# SOM_EVAL_BOARD_V1_1.net
KiCad netlist of a schematic drawn in EAGLE
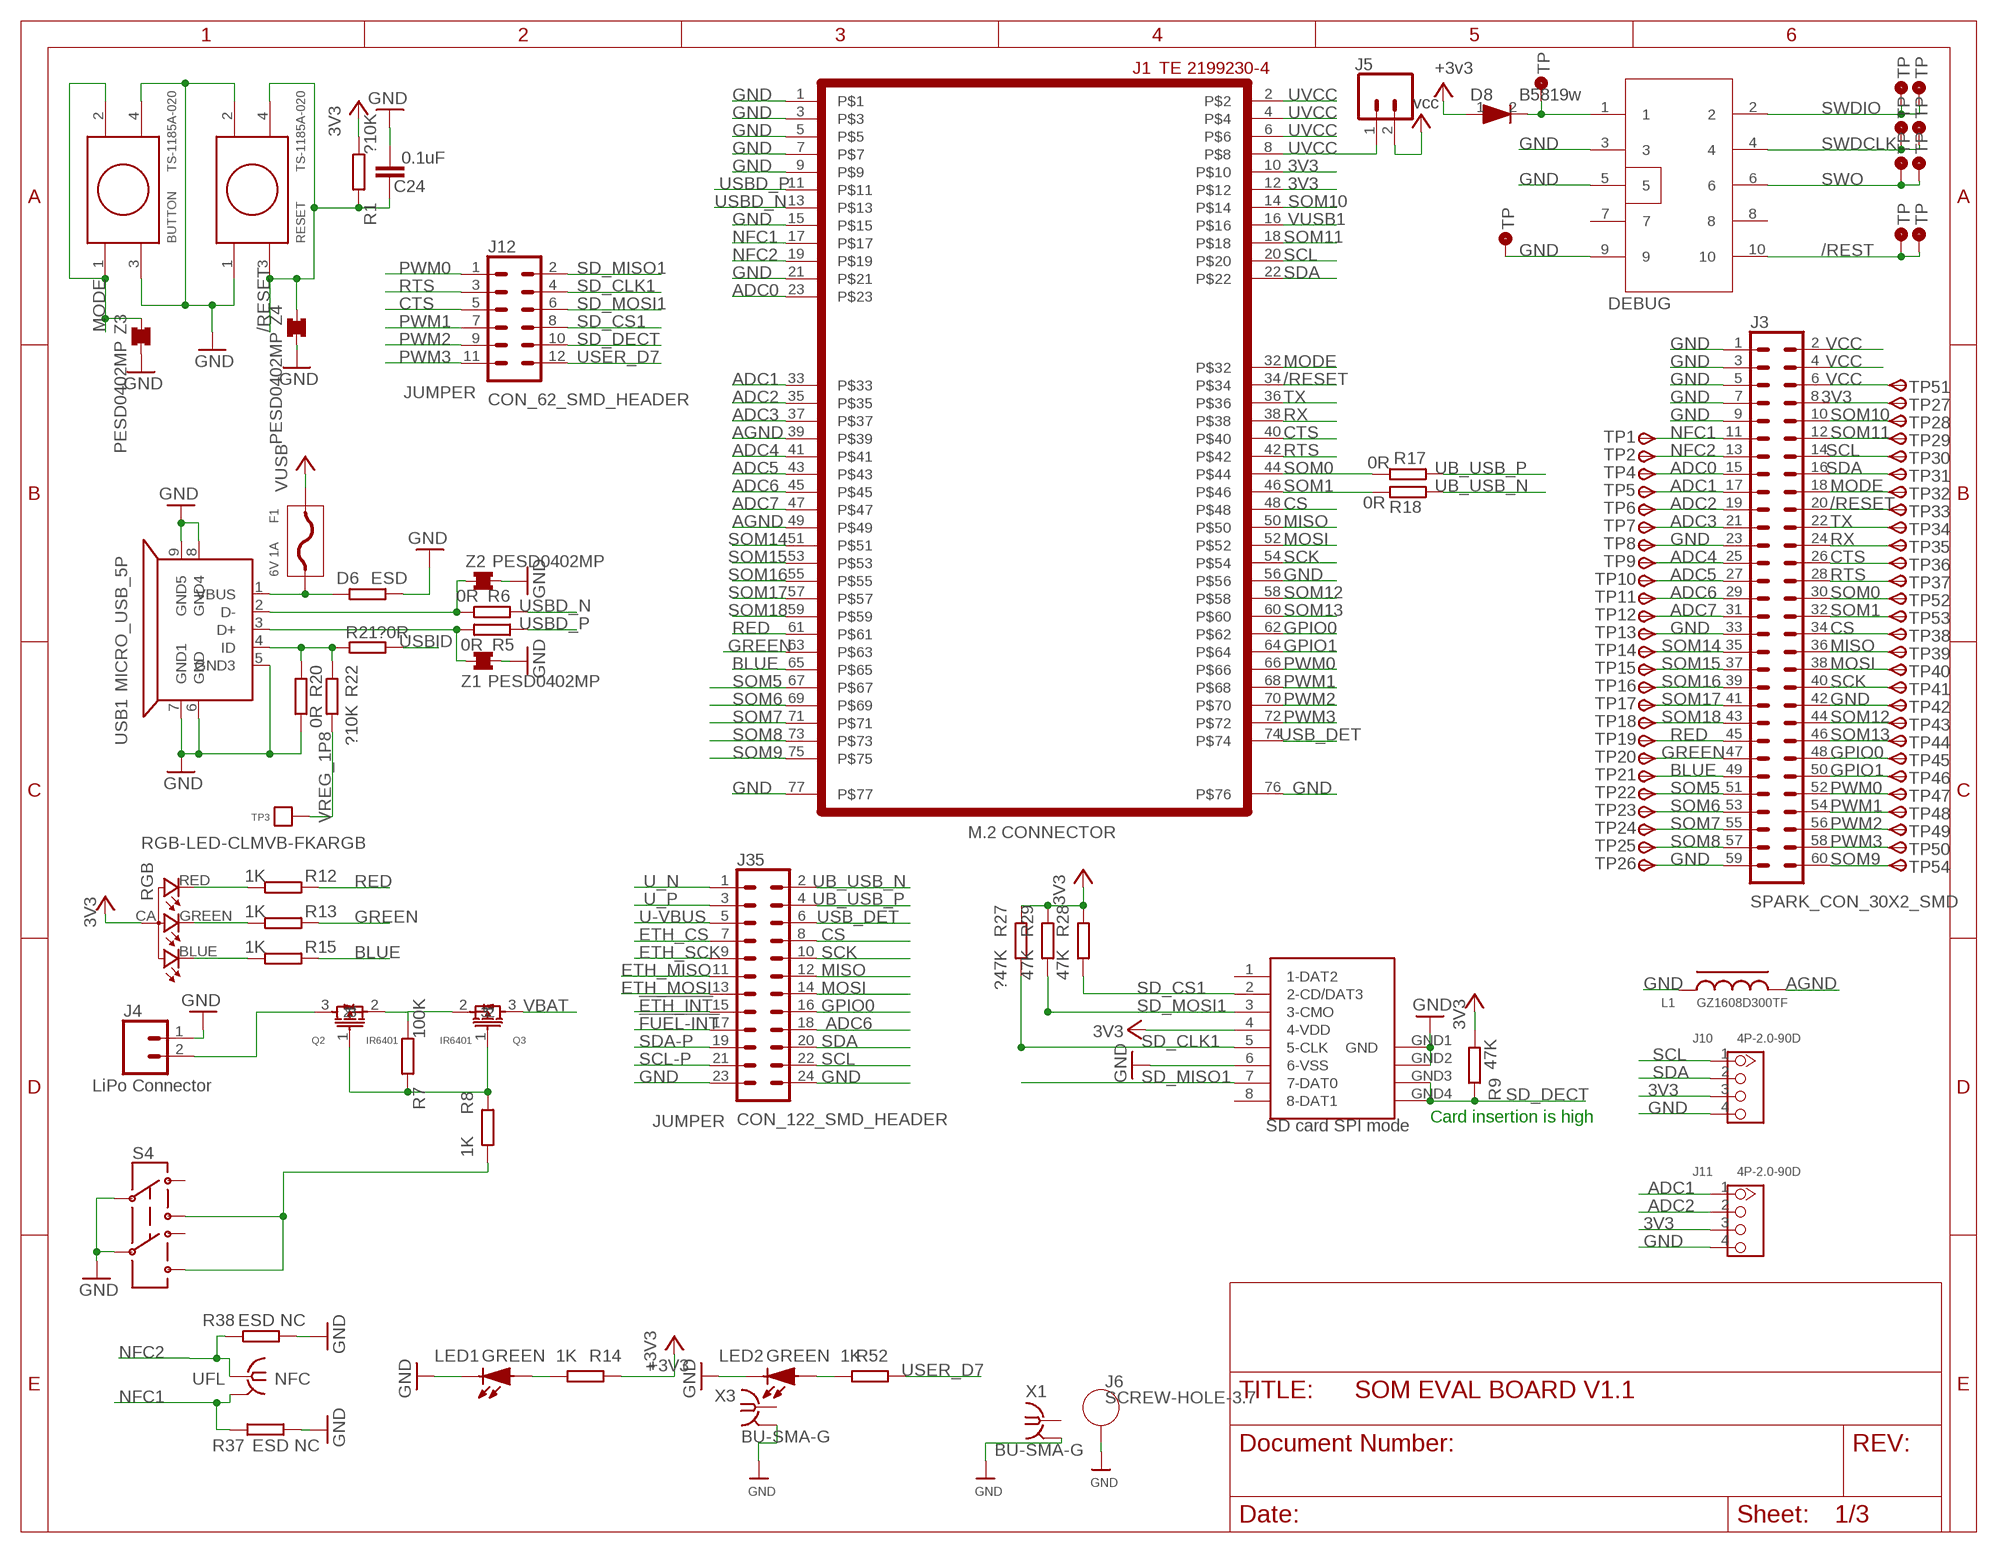
[diagram p0: schematic, sheet 1]
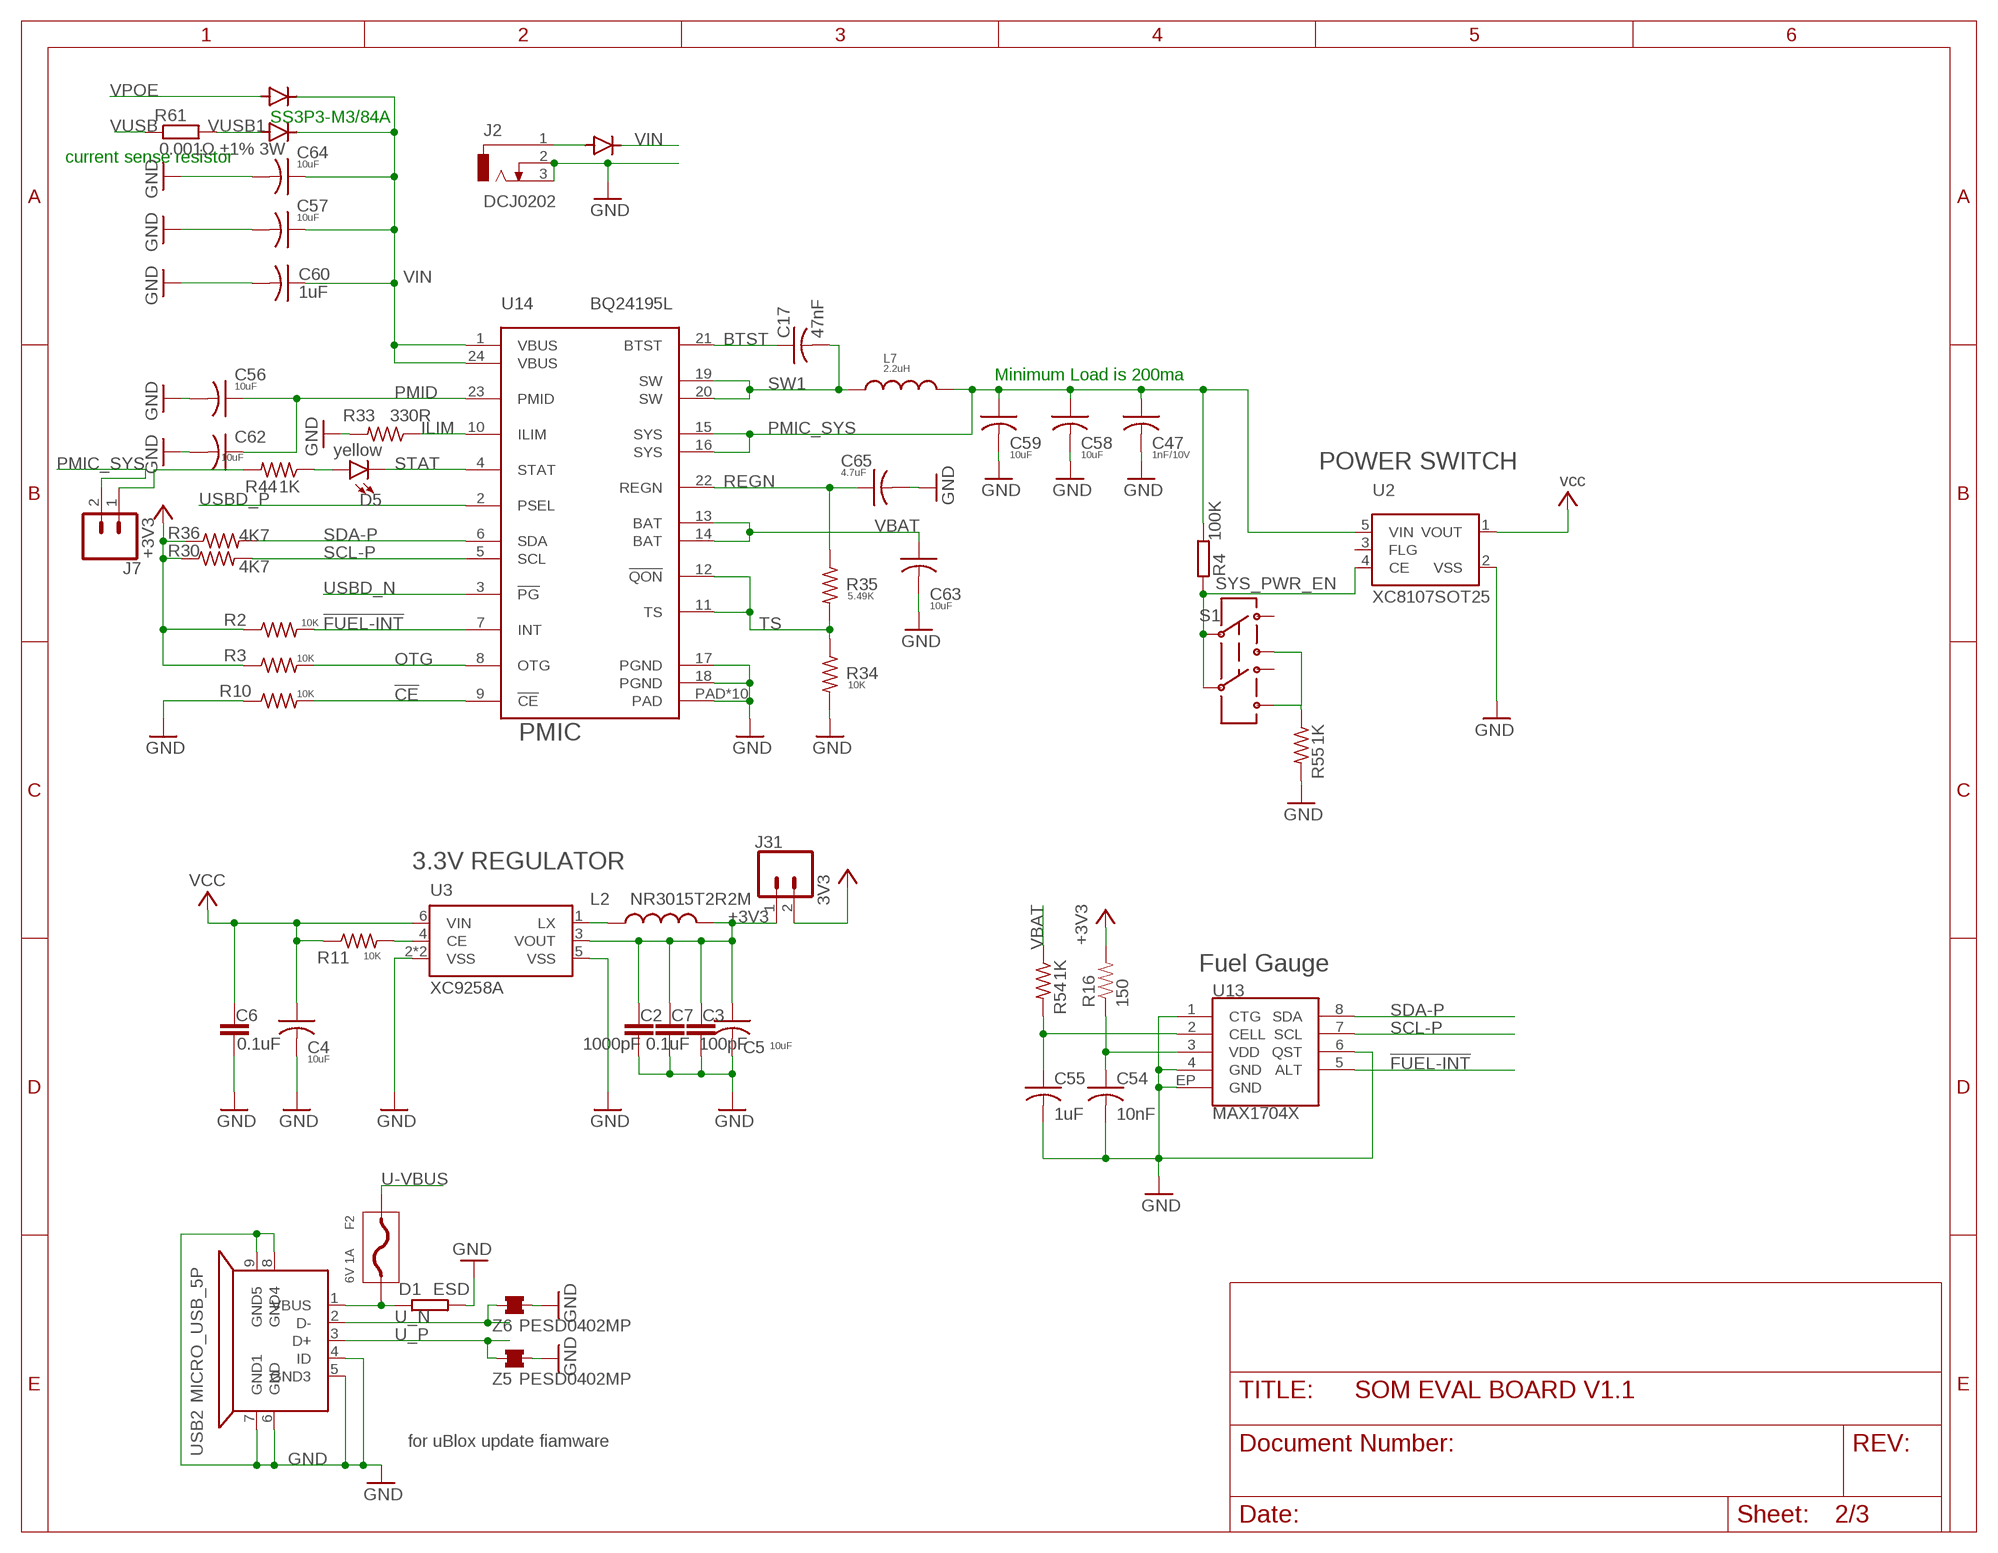
[diagram p1: schematic, sheet 2]
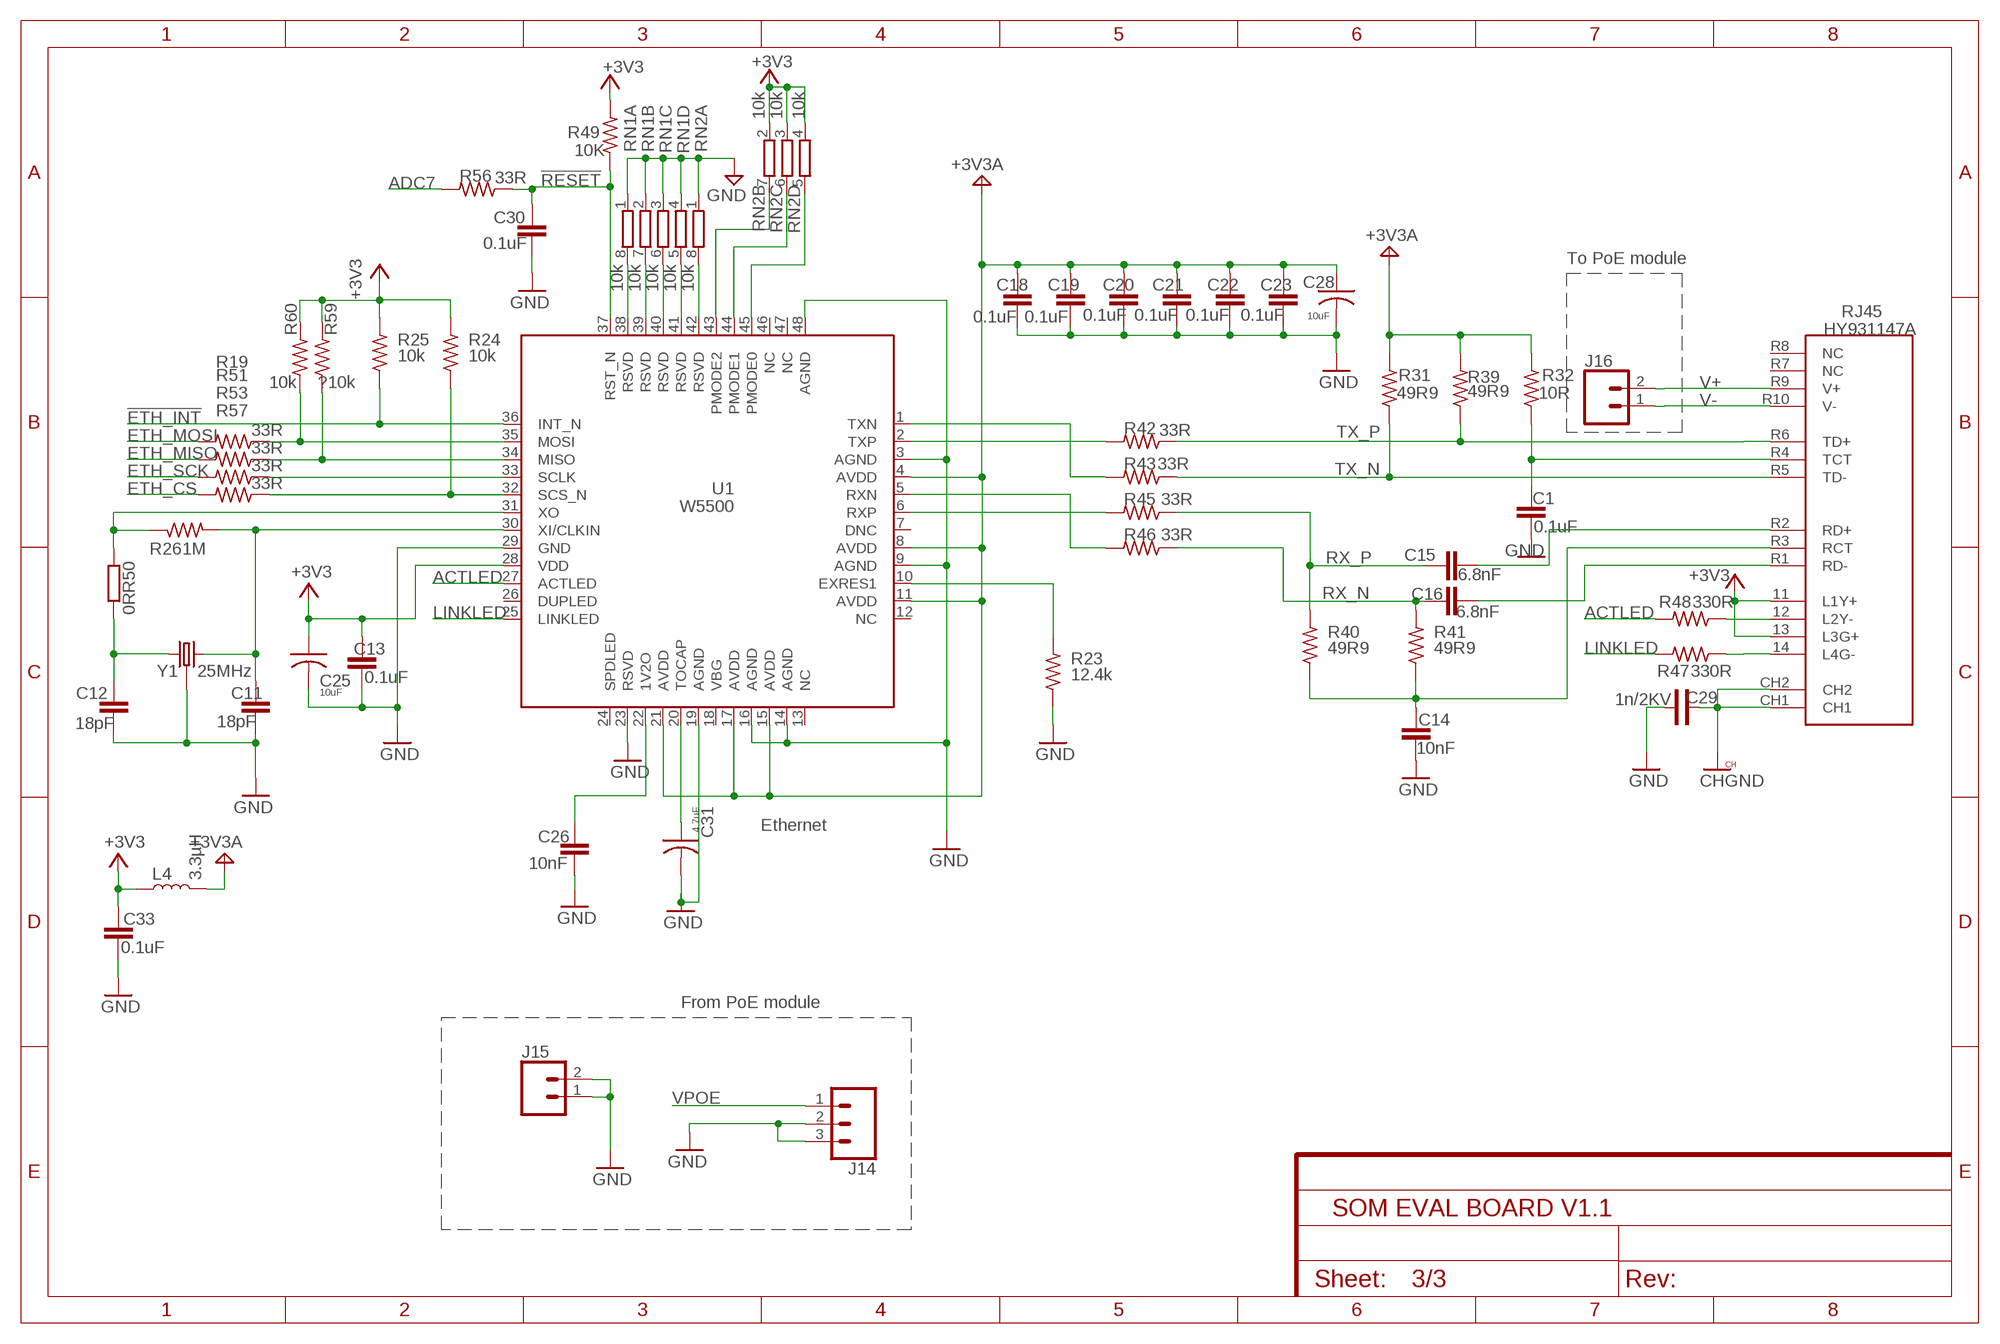
[diagram p2: schematic, sheet 3]

(export (version "E")
  (design (tool "Eeschema 10.0.6"))
  (components
    (comp (ref "C2")
      (value "1000pF")
      (footprint "eagle-import:C0402_B")
      (libsource (lib "eagle-import") (part "CAP_1"))
    )
    (comp (ref "C3")
      (value "100pF")
      (footprint "eagle-import:C0402_B")
      (libsource (lib "eagle-import") (part "CAP_1"))
    )
    (comp (ref "C4")
      (value "10uF")
      (footprint "eagle-import:C0603_B")
      (libsource (lib "eagle-import") (part "C-US0603"))
    )
    (comp (ref "C5")
      (value "10uF")
      (footprint "eagle-import:C0603_B")
      (libsource (lib "eagle-import") (part "C-US0603"))
    )
    (comp (ref "C6")
      (value "0.1uF")
      (footprint "eagle-import:C0402_B")
      (libsource (lib "eagle-import") (part "CAP_1"))
    )
    (comp (ref "C7")
      (value "0.1uF")
      (footprint "eagle-import:C0402_B")
      (libsource (lib "eagle-import") (part "CAP_1"))
    )
    (comp (ref "C17")
      (value "47nF")
      (footprint "eagle-import:C0201_B")
      (libsource (lib "eagle-import") (part "C-USC0201_B"))
    )
    (comp (ref "C47")
      (value "1nF/10V")
      (footprint "eagle-import:C0402_B")
      (libsource (lib "eagle-import") (part "C-US0402"))
    )
    (comp (ref "C54")
      (value "10nF")
      (footprint "eagle-import:C0402_B")
      (libsource (lib "eagle-import") (part "Spark_C-US"))
    )
    (comp (ref "C55")
      (value "1uF")
      (footprint "eagle-import:C0402_B")
      (libsource (lib "eagle-import") (part "Spark_C-US"))
    )
    (comp (ref "C56")
      (value "10uF")
      (footprint "eagle-import:C0603_B")
      (libsource (lib "eagle-import") (part "C-US0603"))
    )
    (comp (ref "C57")
      (value "10uF")
      (footprint "eagle-import:C0603_B")
      (libsource (lib "eagle-import") (part "C-US0603"))
    )
    (comp (ref "C58")
      (value "10uF")
      (footprint "eagle-import:C0603_B")
      (libsource (lib "eagle-import") (part "C-US0603"))
    )
    (comp (ref "C59")
      (value "10uF")
      (footprint "eagle-import:C0603_B")
      (libsource (lib "eagle-import") (part "C-US0603"))
    )
    (comp (ref "C60")
      (value "1uF")
      (footprint "eagle-import:C0402_B")
      (libsource (lib "eagle-import") (part "Spark_C-US"))
    )
    (comp (ref "C62")
      (value "10uF")
      (footprint "eagle-import:C0603_B")
      (libsource (lib "eagle-import") (part "C-US0603"))
    )
    (comp (ref "C63")
      (value "10uF")
      (footprint "eagle-import:C0603_B")
      (libsource (lib "eagle-import") (part "C-US0603"))
    )
    (comp (ref "C64")
      (value "10uF")
      (footprint "eagle-import:C0603_B")
      (libsource (lib "eagle-import") (part "C-US0603"))
    )
    (comp (ref "C65")
      (value "4.7uF")
      (footprint "eagle-import:C0603_B")
      (libsource (lib "eagle-import") (part "C-US0603"))
    )
    (comp (ref "D1")
      (value "ESD")
      (footprint "eagle-import:R-0402S")
      (libsource (lib "eagle-import") (part "RES0402S"))
    )
    (comp (ref "D3")
      (value "SS3P3-M3/84A")
      (footprint "eagle-import:DIODE-DO-220AA_NT(SMP)")
      (libsource (lib "eagle-import") (part "DIODE_NT"))
    )
    (comp (ref "D4")
      (value "SS3P3-M3/84A")
      (footprint "eagle-import:DIODE-DO-220AA_NT(SMP)")
      (libsource (lib "eagle-import") (part "DIODE_NT"))
    )
    (comp (ref "D5")
      (value "yellow")
      (footprint "eagle-import:LED-0603")
      (libsource (lib "eagle-import") (part "LED-RED0603"))
    )
    (comp (ref "D7")
      (value "SS3P3-M3/84A")
      (footprint "eagle-import:DIODE-DO-220AA_NT(SMP)")
      (libsource (lib "eagle-import") (part "DIODE_NT"))
    )
    (comp (ref "F2")
      (value "6V 1A")
      (footprint "eagle-import:F0805")
      (libsource (lib "eagle-import") (part "FUSE"))
    )
    (comp (ref "J2")
      (value "DCJ0202")
      (footprint "eagle-import:DCJ0202")
      (libsource (lib "eagle-import") (part "DCJ0202"))
    )
    (comp (ref "J7")
      (value "CONN_02")
      (footprint "eagle-import:1X02")
      (libsource (lib "eagle-import") (part "SparkFun-Connectors_513_CONN_02"))
    )
    (comp (ref "J31")
      (value "CONN_02")
      (footprint "eagle-import:1X02")
      (libsource (lib "eagle-import") (part "SparkFun-Connectors_513_CONN_02"))
    )
    (comp (ref "L2")
      (value "NR3015T2R2M")
      (footprint "eagle-import:INDUCTOR-VLS-E")
      (libsource (lib "eagle-import") (part "INDUCTOR-SPARKFUNVLS3012ET-4R7M"))
    )
    (comp (ref "L7")
      (value "2.2uH")
      (footprint "eagle-import:INDUCTOR-4040")
      (libsource (lib "eagle-import") (part "INDUCTORI"))
    )
    (comp (ref "R2")
      (value "10K")
      (footprint "eagle-import:R0402_B")
      (libsource (lib "eagle-import") (part "Spark_R-US_"))
    )
    (comp (ref "R3")
      (value "10K")
      (footprint "eagle-import:R0402_B")
      (libsource (lib "eagle-import") (part "Spark_R-US_"))
    )
    (comp (ref "R4")
      (value "100K")
      (footprint "eagle-import:R0603")
      (libsource (lib "eagle-import") (part "RESR0603"))
    )
    (comp (ref "R10")
      (value "10K")
      (footprint "eagle-import:R0402_B")
      (libsource (lib "eagle-import") (part "Spark_R-US_"))
    )
    (comp (ref "R11")
      (value "10K")
      (footprint "eagle-import:R0402_B")
      (libsource (lib "eagle-import") (part "Spark_R-US_"))
    )
    (comp (ref "R16")
      (value "150")
      (footprint "eagle-import:0402-RES")
      (libsource (lib "eagle-import") (part "RESISTOR0402-RES"))
    )
    (comp (ref "R30")
      (value "4K7")
      (footprint "eagle-import:C0201_B")
      (libsource (lib "eagle-import") (part "R-US_R0201_B"))
    )
    (comp (ref "R33")
      (value "330R")
      (footprint "eagle-import:R0402_B")
      (libsource (lib "eagle-import") (part "R-US_"))
    )
    (comp (ref "R34")
      (value "10K")
      (footprint "eagle-import:R0402_B")
      (libsource (lib "eagle-import") (part "Spark_R-US_"))
    )
    (comp (ref "R35")
      (value "5.49K")
      (footprint "eagle-import:R0402_B")
      (libsource (lib "eagle-import") (part "Spark_R-US_"))
    )
    (comp (ref "R36")
      (value "4K7")
      (footprint "eagle-import:C0201_B")
      (libsource (lib "eagle-import") (part "R-US_R0201_B"))
    )
    (comp (ref "R44")
      (value "1K")
      (footprint "eagle-import:R0402_B")
      (libsource (lib "eagle-import") (part "R-US_"))
    )
    (comp (ref "R54")
      (value "1K")
      (footprint "eagle-import:R0402_B")
      (libsource (lib "eagle-import") (part "R-US_"))
    )
    (comp (ref "R55")
      (value "1K")
      (footprint "eagle-import:R0402_B")
      (libsource (lib "eagle-import") (part "R-US_"))
    )
    (comp (ref "R61")
      (value "0.001Ω ±1% 3W")
      (footprint "eagle-import:R2512")
      (libsource (lib "eagle-import") (part "R-EU_R2512"))
    )
    (comp (ref "S1")
      (value "SWITCH-DPDT")
      (footprint "eagle-import:SWITCH-2.5X3.2-6")
      (libsource (lib "eagle-import") (part "SWITCH-DPDT"))
    )
    (comp (ref "U2")
      (value "XC8107SOT25")
      (footprint "eagle-import:SOT25")
      (libsource (lib "eagle-import") (part "XC8107SOT25"))
    )
    (comp (ref "U3")
      (value "XC9258A")
      (footprint "eagle-import:USP-6C")
      (libsource (lib "eagle-import") (part "XC9258A33EER-G"))
    )
    (comp (ref "U13")
      (value "MAX1704X")
      (footprint "eagle-import:TDFN-8")
      (libsource (lib "eagle-import") (part "MAX1704X"))
    )
    (comp (ref "U14")
      (value "BQ24195L")
      (footprint "eagle-import:QFN24")
      (libsource (lib "eagle-import") (part "BQ24298RTWR"))
    )
    (comp (ref "USB2")
      (value "MICRO_USB_5P")
      (footprint "eagle-import:MICRO_USB")
      (libsource (lib "eagle-import") (part "MICRO_USBMICRO_USB"))
    )
    (comp (ref "Z5")
      (value "PESD0402MP")
      (footprint "eagle-import:SMD-0402MP")
      (libsource (lib "eagle-import") (part "PESD0402MP"))
    )
    (comp (ref "Z6")
      (value "PESD0402MP")
      (footprint "eagle-import:SMD-0402MP")
      (libsource (lib "eagle-import") (part "PESD0402MP"))
    )
    (comp (ref "BUTTON")
      (value "TS-1185A-020")
      (footprint "eagle-import:TS-1185A-020")
      (libsource (lib "eagle-import") (part "TS-1185A-020"))
    )
    (comp (ref "C24")
      (value "0.1uF")
      (footprint "eagle-import:C0402_B")
      (libsource (lib "eagle-import") (part "CAP_1"))
    )
    (comp (ref "D6")
      (value "ESD")
      (footprint "eagle-import:R-0402S")
      (libsource (lib "eagle-import") (part "RES0402S"))
    )
    (comp (ref "D8")
      (value "B5819w")
      (footprint "eagle-import:SOD-123")
      (libsource (lib "eagle-import") (part "DIODESOD123"))
    )
    (comp (ref "DEBUG")
      (value "CON5X2")
      (footprint "eagle-import:CON5X2_1.27")
      (libsource (lib "eagle-import") (part "CON5X2"))
    )
    (comp (ref "F1")
      (value "6V 1A")
      (footprint "eagle-import:F0805")
      (libsource (lib "eagle-import") (part "FUSE"))
    )
    (comp (ref "J1")
      (value "TE 2199230-4")
      (footprint "eagle-import:M.2EKEY")
      (libsource (lib "eagle-import") (part "M.2EKEY"))
    )
    (comp (ref "J3")
      (value "SPARK_CON_30X2_SMD")
      (footprint "eagle-import:SPARK_CON_30X2_SMD")
      (libsource (lib "eagle-import") (part "SPARK_CON_30X2_SMD"))
    )
    (comp (ref "J4")
      (value "CONN_02-JST-2MM-SMT")
      (footprint "eagle-import:JST-2-SMD")
      (libsource (lib "eagle-import") (part "CONN_02-JST-2MM-SMT"))
    )
    (comp (ref "J5")
      (value "CONN_02")
      (footprint "eagle-import:1X02")
      (libsource (lib "eagle-import") (part "SparkFun-Connectors_513_CONN_02"))
    )
    (comp (ref "J6")
      (value "SCREW-HOLE-3.7")
      (footprint "eagle-import:SCREW-HOLE-3.7")
      (libsource (lib "eagle-import") (part "SCREW-HOLE-3.7"))
    )
    (comp (ref "J10")
      (value "4P-2.0-90D")
      (footprint "eagle-import:HW4-2.0-90D")
      (libsource (lib "eagle-import") (part "GROVE-CONNECTOR-DIP-90D(4P-2.0)"))
    )
    (comp (ref "J11")
      (value "4P-2.0-90D")
      (footprint "eagle-import:HW4-2.0-90D")
      (libsource (lib "eagle-import") (part "GROVE-CONNECTOR-DIP-90D(4P-2.0)"))
    )
    (comp (ref "J12")
      (value "CON_62_SMD_HEADER")
      (footprint "eagle-import:CON_6_2_SMD_HEADER")
      (libsource (lib "eagle-import") (part "CON_62_SMD_HEADER"))
    )
    (comp (ref "J35")
      (value "CON_122_SMD_HEADER")
      (footprint "eagle-import:CON_12_2_SMD_HEADER")
      (libsource (lib "eagle-import") (part "CON_122_SMD_HEADER"))
    )
    (comp (ref "L1")
      (value "GZ1608D300TF")
      (footprint "eagle-import:R-0603A")
      (libsource (lib "eagle-import") (part "L"))
    )
    (comp (ref "LED1")
      (value "GREEN")
      (footprint "eagle-import:LED0603")
      (libsource (lib "eagle-import") (part "LED"))
    )
    (comp (ref "LED2")
      (value "GREEN")
      (footprint "eagle-import:LED0603")
      (libsource (lib "eagle-import") (part "LED"))
    )
    (comp (ref "NFC")
      (value "UFL")
      (footprint "eagle-import:IPEX-20279-001E")
      (libsource (lib "eagle-import") (part "IPEX-20279-001E"))
    )
    (comp (ref "P1")
      (value "SPARK_POGOPIN")
      (footprint "eagle-import:SPARK_POGO-2.0")
      (libsource (lib "eagle-import") (part "SPARK_POGOPIN"))
    )
    (comp (ref "P2")
      (value "SPARK_POGOPIN")
      (footprint "eagle-import:SPARK_POGO-2.0")
      (libsource (lib "eagle-import") (part "SPARK_POGOPIN"))
    )
    (comp (ref "P3")
      (value "SPARK_POGOPIN")
      (footprint "eagle-import:SPARK_POGO-2.0")
      (libsource (lib "eagle-import") (part "SPARK_POGOPIN"))
    )
    (comp (ref "P4")
      (value "SPARK_POGOPIN")
      (footprint "eagle-import:SPARK_POGO-2.0")
      (libsource (lib "eagle-import") (part "SPARK_POGOPIN"))
    )
    (comp (ref "Q2")
      (value "IR6401")
      (footprint "eagle-import:SOT-23")
      (libsource (lib "eagle-import") (part "PMOS"))
    )
    (comp (ref "Q3")
      (value "IR6401")
      (footprint "eagle-import:SOT-23")
      (libsource (lib "eagle-import") (part "PMOS"))
    )
    (comp (ref "R1")
      (value "?10K")
      (footprint "eagle-import:R-0402S")
      (libsource (lib "eagle-import") (part "RES0402S"))
    )
    (comp (ref "R5")
      (value "0R")
      (footprint "eagle-import:R-0402S")
      (libsource (lib "eagle-import") (part "RES0402S"))
    )
    (comp (ref "R6")
      (value "0R")
      (footprint "eagle-import:R-0402S")
      (libsource (lib "eagle-import") (part "RES0402S"))
    )
    (comp (ref "R7")
      (value "100K")
      (footprint "eagle-import:R0603")
      (libsource (lib "eagle-import") (part "RESR0603"))
    )
    (comp (ref "R8")
      (value "1K")
      (footprint "eagle-import:R-0402S")
      (libsource (lib "eagle-import") (part "RES0402S"))
    )
    (comp (ref "R9")
      (value "47K")
      (footprint "eagle-import:R-0402S")
      (libsource (lib "eagle-import") (part "RES0402S"))
    )
    (comp (ref "R12")
      (value "1K")
      (footprint "eagle-import:R-0402S")
      (libsource (lib "eagle-import") (part "RES0402S"))
    )
    (comp (ref "R13")
      (value "1K")
      (footprint "eagle-import:R-0402S")
      (libsource (lib "eagle-import") (part "RES0402S"))
    )
    (comp (ref "R14")
      (value "1K")
      (footprint "eagle-import:R-0402S")
      (libsource (lib "eagle-import") (part "RES0402S"))
    )
    (comp (ref "R15")
      (value "1K")
      (footprint "eagle-import:R-0402S")
      (libsource (lib "eagle-import") (part "RES0402S"))
    )
    (comp (ref "R17")
      (value "0R")
      (footprint "eagle-import:R-0402S")
      (libsource (lib "eagle-import") (part "RES0402S"))
    )
    (comp (ref "R18")
      (value "0R")
      (footprint "eagle-import:R-0402S")
      (libsource (lib "eagle-import") (part "RES0402S"))
    )
    (comp (ref "R20")
      (value "0R")
      (footprint "eagle-import:R-0402S")
      (libsource (lib "eagle-import") (part "RES0402S"))
    )
    (comp (ref "R21")
      (value "?0R")
      (footprint "eagle-import:R-0402S")
      (libsource (lib "eagle-import") (part "RES0402S"))
    )
    (comp (ref "R22")
      (value "?10K")
      (footprint "eagle-import:R-0402S")
      (libsource (lib "eagle-import") (part "RES0402S"))
    )
    (comp (ref "R27")
      (value "?47K")
      (footprint "eagle-import:R-0402S")
      (libsource (lib "eagle-import") (part "RES0402S"))
    )
    (comp (ref "R28")
      (value "47K")
      (footprint "eagle-import:R-0402S")
      (libsource (lib "eagle-import") (part "RES0402S"))
    )
    (comp (ref "R29")
      (value "47K")
      (footprint "eagle-import:R-0402S")
      (libsource (lib "eagle-import") (part "RES0402S"))
    )
    (comp (ref "R37")
      (value "ESD NC")
      (footprint "eagle-import:R-0402S")
      (libsource (lib "eagle-import") (part "RES0402S"))
    )
    (comp (ref "R38")
      (value "ESD NC")
      (footprint "eagle-import:R-0402S")
      (libsource (lib "eagle-import") (part "RES0402S"))
    )
    (comp (ref "R52")
      (value "1K")
      (footprint "eagle-import:R-0402S")
      (libsource (lib "eagle-import") (part "RES0402S"))
    )
    (comp (ref "RESET")
      (value "TS-1185A-020")
      (footprint "eagle-import:TS-1185A-020")
      (libsource (lib "eagle-import") (part "TS-1185A-020"))
    )
    (comp (ref "RGB")
      (value "RGB-LED-CLMVB-FKARGB")
      (footprint "eagle-import:PLCC4-2MM-RGB")
      (libsource (lib "eagle-import") (part "RGB-LED-CLMVB-FKARGB"))
    )
    (comp (ref "S4")
      (value "SWITCH-DPDT")
      (footprint "eagle-import:SWITCH-2.5X3.2-6")
      (libsource (lib "eagle-import") (part "SWITCH-DPDT"))
    )
    (comp (ref "TP1")
      (value "TPSB1,27")
      (footprint "eagle-import:B1,27")
      (libsource (lib "eagle-import") (part "TPSB1,27"))
    )
    (comp (ref "TP2")
      (value "TPSB1,27")
      (footprint "eagle-import:B1,27")
      (libsource (lib "eagle-import") (part "TPSB1,27"))
    )
    (comp (ref "TP3")
      (value "TPTP")
      (footprint "eagle-import:TP")
      (libsource (lib "eagle-import") (part "TPTP"))
    )
    (comp (ref "TP4")
      (value "TPSB1,27")
      (footprint "eagle-import:B1,27")
      (libsource (lib "eagle-import") (part "TPSB1,27"))
    )
    (comp (ref "TP5")
      (value "TPSB1,27")
      (footprint "eagle-import:B1,27")
      (libsource (lib "eagle-import") (part "TPSB1,27"))
    )
    (comp (ref "TP6")
      (value "TPSB1,27")
      (footprint "eagle-import:B1,27")
      (libsource (lib "eagle-import") (part "TPSB1,27"))
    )
    (comp (ref "TP7")
      (value "TPSB1,27")
      (footprint "eagle-import:B1,27")
      (libsource (lib "eagle-import") (part "TPSB1,27"))
    )
    (comp (ref "TP8")
      (value "TPSB1,27")
      (footprint "eagle-import:B1,27")
      (libsource (lib "eagle-import") (part "TPSB1,27"))
    )
    (comp (ref "TP9")
      (value "TPSB1,27")
      (footprint "eagle-import:B1,27")
      (libsource (lib "eagle-import") (part "TPSB1,27"))
    )
    (comp (ref "TP10")
      (value "TPSB1,27")
      (footprint "eagle-import:B1,27")
      (libsource (lib "eagle-import") (part "TPSB1,27"))
    )
    (comp (ref "TP11")
      (value "TPSB1,27")
      (footprint "eagle-import:B1,27")
      (libsource (lib "eagle-import") (part "TPSB1,27"))
    )
    (comp (ref "TP12")
      (value "TPSB1,27")
      (footprint "eagle-import:B1,27")
      (libsource (lib "eagle-import") (part "TPSB1,27"))
    )
    (comp (ref "TP13")
      (value "TPSB1,27")
      (footprint "eagle-import:B1,27")
      (libsource (lib "eagle-import") (part "TPSB1,27"))
    )
    (comp (ref "TP14")
      (value "TPSB1,27")
      (footprint "eagle-import:B1,27")
      (libsource (lib "eagle-import") (part "TPSB1,27"))
    )
    (comp (ref "TP15")
      (value "TPSB1,27")
      (footprint "eagle-import:B1,27")
      (libsource (lib "eagle-import") (part "TPSB1,27"))
    )
    (comp (ref "TP16")
      (value "TPSB1,27")
      (footprint "eagle-import:B1,27")
      (libsource (lib "eagle-import") (part "TPSB1,27"))
    )
    (comp (ref "TP17")
      (value "TPSB1,27")
      (footprint "eagle-import:B1,27")
      (libsource (lib "eagle-import") (part "TPSB1,27"))
    )
    (comp (ref "TP18")
      (value "TPSB1,27")
      (footprint "eagle-import:B1,27")
      (libsource (lib "eagle-import") (part "TPSB1,27"))
    )
    (comp (ref "TP19")
      (value "TPSB1,27")
      (footprint "eagle-import:B1,27")
      (libsource (lib "eagle-import") (part "TPSB1,27"))
    )
    (comp (ref "TP20")
      (value "TPSB1,27")
      (footprint "eagle-import:B1,27")
      (libsource (lib "eagle-import") (part "TPSB1,27"))
    )
    (comp (ref "TP21")
      (value "TPSB1,27")
      (footprint "eagle-import:B1,27")
      (libsource (lib "eagle-import") (part "TPSB1,27"))
    )
    (comp (ref "TP22")
      (value "TPSB1,27")
      (footprint "eagle-import:B1,27")
      (libsource (lib "eagle-import") (part "TPSB1,27"))
    )
    (comp (ref "TP23")
      (value "TPSB1,27")
      (footprint "eagle-import:B1,27")
      (libsource (lib "eagle-import") (part "TPSB1,27"))
    )
    (comp (ref "TP24")
      (value "TPSB1,27")
      (footprint "eagle-import:B1,27")
      (libsource (lib "eagle-import") (part "TPSB1,27"))
    )
    (comp (ref "TP25")
      (value "TPSB1,27")
      (footprint "eagle-import:B1,27")
      (libsource (lib "eagle-import") (part "TPSB1,27"))
    )
    (comp (ref "TP26")
      (value "TPSB1,27")
      (footprint "eagle-import:B1,27")
      (libsource (lib "eagle-import") (part "TPSB1,27"))
    )
    (comp (ref "TP27")
      (value "TPSB1,27")
      (footprint "eagle-import:B1,27")
      (libsource (lib "eagle-import") (part "TPSB1,27"))
    )
    (comp (ref "TP28")
      (value "TPSB1,27")
      (footprint "eagle-import:B1,27")
      (libsource (lib "eagle-import") (part "TPSB1,27"))
    )
    (comp (ref "TP29")
      (value "TPSB1,27")
      (footprint "eagle-import:B1,27")
      (libsource (lib "eagle-import") (part "TPSB1,27"))
    )
    (comp (ref "TP30")
      (value "TPSB1,27")
      (footprint "eagle-import:B1,27")
      (libsource (lib "eagle-import") (part "TPSB1,27"))
    )
    (comp (ref "TP31")
      (value "TPSB1,27")
      (footprint "eagle-import:B1,27")
      (libsource (lib "eagle-import") (part "TPSB1,27"))
    )
    (comp (ref "TP32")
      (value "TPSB1,27")
      (footprint "eagle-import:B1,27")
      (libsource (lib "eagle-import") (part "TPSB1,27"))
    )
    (comp (ref "TP33")
      (value "TPSB1,27")
      (footprint "eagle-import:B1,27")
      (libsource (lib "eagle-import") (part "TPSB1,27"))
    )
    (comp (ref "TP34")
      (value "TPSB1,27")
      (footprint "eagle-import:B1,27")
      (libsource (lib "eagle-import") (part "TPSB1,27"))
    )
    (comp (ref "TP35")
      (value "TPSB1,27")
      (footprint "eagle-import:B1,27")
      (libsource (lib "eagle-import") (part "TPSB1,27"))
    )
    (comp (ref "TP36")
      (value "TPSB1,27")
      (footprint "eagle-import:B1,27")
      (libsource (lib "eagle-import") (part "TPSB1,27"))
    )
    (comp (ref "TP37")
      (value "TPSB1,27")
      (footprint "eagle-import:B1,27")
      (libsource (lib "eagle-import") (part "TPSB1,27"))
    )
    (comp (ref "TP38")
      (value "TPSB1,27")
      (footprint "eagle-import:B1,27")
      (libsource (lib "eagle-import") (part "TPSB1,27"))
    )
    (comp (ref "TP39")
      (value "TPSB1,27")
      (footprint "eagle-import:B1,27")
      (libsource (lib "eagle-import") (part "TPSB1,27"))
    )
    (comp (ref "TP40")
      (value "TPSB1,27")
      (footprint "eagle-import:B1,27")
      (libsource (lib "eagle-import") (part "TPSB1,27"))
    )
    (comp (ref "TP41")
      (value "TPSB1,27")
      (footprint "eagle-import:B1,27")
      (libsource (lib "eagle-import") (part "TPSB1,27"))
    )
    (comp (ref "TP42")
      (value "TPSB1,27")
      (footprint "eagle-import:B1,27")
      (libsource (lib "eagle-import") (part "TPSB1,27"))
    )
    (comp (ref "TP43")
      (value "TPSB1,27")
      (footprint "eagle-import:B1,27")
      (libsource (lib "eagle-import") (part "TPSB1,27"))
    )
    (comp (ref "TP44")
      (value "TPSB1,27")
      (footprint "eagle-import:B1,27")
      (libsource (lib "eagle-import") (part "TPSB1,27"))
    )
    (comp (ref "TP45")
      (value "TPSB1,27")
      (footprint "eagle-import:B1,27")
      (libsource (lib "eagle-import") (part "TPSB1,27"))
    )
    (comp (ref "TP46")
      (value "TPSB1,27")
      (footprint "eagle-import:B1,27")
      (libsource (lib "eagle-import") (part "TPSB1,27"))
    )
    (comp (ref "TP47")
      (value "TPSB1,27")
      (footprint "eagle-import:B1,27")
      (libsource (lib "eagle-import") (part "TPSB1,27"))
    )
    (comp (ref "TP48")
      (value "TPSB1,27")
      (footprint "eagle-import:B1,27")
      (libsource (lib "eagle-import") (part "TPSB1,27"))
    )
    (comp (ref "TP49")
      (value "TPSB1,27")
      (footprint "eagle-import:B1,27")
      (libsource (lib "eagle-import") (part "TPSB1,27"))
    )
    (comp (ref "TP50")
      (value "TPSB1,27")
      (footprint "eagle-import:B1,27")
      (libsource (lib "eagle-import") (part "TPSB1,27"))
    )
    (comp (ref "TP51")
      (value "TPSB1,27")
      (footprint "eagle-import:B1,27")
      (libsource (lib "eagle-import") (part "TPSB1,27"))
    )
    (comp (ref "TP52")
      (value "TPSB1,27")
      (footprint "eagle-import:B1,27")
      (libsource (lib "eagle-import") (part "TPSB1,27"))
    )
    (comp (ref "TP53")
      (value "TPSB1,27")
      (footprint "eagle-import:B1,27")
      (libsource (lib "eagle-import") (part "TPSB1,27"))
    )
    (comp (ref "TP54")
      (value "TPSB1,27")
      (footprint "eagle-import:B1,27")
      (libsource (lib "eagle-import") (part "TPSB1,27"))
    )
    (comp (ref "U$1")
      (value "TP2")
      (footprint "eagle-import:TP70_BOT")
      (libsource (lib "eagle-import") (part "TP2"))
    )
    (comp (ref "U$2")
      (value "TP2")
      (footprint "eagle-import:TP70_BOT")
      (libsource (lib "eagle-import") (part "TP2"))
    )
    (comp (ref "U$9")
      (value "TP2")
      (footprint "eagle-import:TP70_BOT")
      (libsource (lib "eagle-import") (part "TP2"))
    )
    (comp (ref "U$10")
      (value "TP2")
      (footprint "eagle-import:TP70_BOT")
      (libsource (lib "eagle-import") (part "TP2"))
    )
    (comp (ref "U$11")
      (value "TP2")
      (footprint "eagle-import:TP70_BOT")
      (libsource (lib "eagle-import") (part "TP2"))
    )
    (comp (ref "U$12")
      (value "TP2")
      (footprint "eagle-import:TP70_BOT")
      (libsource (lib "eagle-import") (part "TP2"))
    )
    (comp (ref "USB1")
      (value "MICRO_USB_5P")
      (footprint "eagle-import:MICRO_USB")
      (libsource (lib "eagle-import") (part "MICRO_USBMICRO_USB"))
    )
    (comp (ref "X1")
      (value "BU-SMA-G")
      (footprint "eagle-import:BU-SMA-G")
      (libsource (lib "eagle-import") (part "BU-SMA-G"))
    )
    (comp (ref "X3")
      (value "BU-SMA-G")
      (footprint "eagle-import:BU-SMA-G")
      (libsource (lib "eagle-import") (part "BU-SMA-G"))
    )
    (comp (ref "X4")
      (value "0046_15TW-882")
      (footprint "eagle-import:SDCARD-15TW-8821")
      (fields (field (name "PART_NUMBER") "15TW-882 REEL"))
      (libsource (lib "eagle-import") (part "0046_15TW-882"))
    )
    (comp (ref "Z1")
      (value "PESD0402MP")
      (footprint "eagle-import:SMD-0402MP")
      (libsource (lib "eagle-import") (part "PESD0402MP"))
    )
    (comp (ref "Z2")
      (value "PESD0402MP")
      (footprint "eagle-import:SMD-0402MP")
      (libsource (lib "eagle-import") (part "PESD0402MP"))
    )
    (comp (ref "Z3")
      (value "PESD0402MP")
      (footprint "eagle-import:SMD-0402MP")
      (libsource (lib "eagle-import") (part "PESD0402MP"))
    )
    (comp (ref "Z4")
      (value "PESD0402MP")
      (footprint "eagle-import:SMD-0402MP")
      (libsource (lib "eagle-import") (part "PESD0402MP"))
    )
    (comp (ref "C1")
      (value "0.1uF")
      (footprint "eagle-import:C0402_B")
      (libsource (lib "eagle-import") (part "CAP_1"))
    )
    (comp (ref "C11")
      (value "18pF")
      (footprint "eagle-import:C0402_B")
      (libsource (lib "eagle-import") (part "CAP_1"))
    )
    (comp (ref "C12")
      (value "18pF")
      (footprint "eagle-import:C0402_B")
      (libsource (lib "eagle-import") (part "CAP_1"))
    )
    (comp (ref "C13")
      (value "0.1uF")
      (footprint "eagle-import:C0402_B")
      (libsource (lib "eagle-import") (part "CAP_1"))
    )
    (comp (ref "C14")
      (value "10nF")
      (footprint "eagle-import:C0402_B")
      (libsource (lib "eagle-import") (part "CAP_1"))
    )
    (comp (ref "C15")
      (value "6.8nF")
      (footprint "eagle-import:C0402_B")
      (libsource (lib "eagle-import") (part "CAP_1"))
    )
    (comp (ref "C16")
      (value "6.8nF")
      (footprint "eagle-import:C0402_B")
      (libsource (lib "eagle-import") (part "CAP_1"))
    )
    (comp (ref "C18")
      (value "0.1uF")
      (footprint "eagle-import:C0402_B")
      (libsource (lib "eagle-import") (part "CAP_1"))
    )
    (comp (ref "C19")
      (value "0.1uF")
      (footprint "eagle-import:C0402_B")
      (libsource (lib "eagle-import") (part "CAP_1"))
    )
    (comp (ref "C20")
      (value "0.1uF")
      (footprint "eagle-import:C0402_B")
      (libsource (lib "eagle-import") (part "CAP_1"))
    )
    (comp (ref "C21")
      (value "0.1uF")
      (footprint "eagle-import:C0402_B")
      (libsource (lib "eagle-import") (part "CAP_1"))
    )
    (comp (ref "C22")
      (value "0.1uF")
      (footprint "eagle-import:C0402_B")
      (libsource (lib "eagle-import") (part "CAP_1"))
    )
    (comp (ref "C23")
      (value "0.1uF")
      (footprint "eagle-import:C0402_B")
      (libsource (lib "eagle-import") (part "CAP_1"))
    )
    (comp (ref "C25")
      (value "10uF")
      (footprint "eagle-import:C0603_B")
      (libsource (lib "eagle-import") (part "C-US0603"))
    )
    (comp (ref "C26")
      (value "10nF")
      (footprint "eagle-import:C0402_B")
      (libsource (lib "eagle-import") (part "CAP_1"))
    )
    (comp (ref "C28")
      (value "10uF")
      (footprint "eagle-import:C0603_B")
      (libsource (lib "eagle-import") (part "C-US0603"))
    )
    (comp (ref "C29")
      (value "1n/2KV")
      (footprint "eagle-import:C-1808")
      (libsource (lib "eagle-import") (part "C-1808"))
    )
    (comp (ref "C30")
      (value "0.1uF")
      (footprint "eagle-import:C0402_B")
      (libsource (lib "eagle-import") (part "CAP_1"))
    )
    (comp (ref "C31")
      (value "4.7uF")
      (footprint "eagle-import:C0603_B")
      (libsource (lib "eagle-import") (part "C-US0603"))
    )
    (comp (ref "C33")
      (value "0.1uF")
      (footprint "eagle-import:C0402_B")
      (libsource (lib "eagle-import") (part "CAP_1"))
    )
    (comp (ref "J14")
      (value "CONN_03")
      (footprint "eagle-import:1X03")
      (libsource (lib "eagle-import") (part "CONN_03"))
    )
    (comp (ref "J15")
      (value "CONN_02")
      (footprint "eagle-import:1X02")
      (libsource (lib "eagle-import") (part "SparkFun-Connectors_513_CONN_02"))
    )
    (comp (ref "J16")
      (value "CONN_02")
      (footprint "eagle-import:1X02")
      (libsource (lib "eagle-import") (part "SparkFun-Connectors_513_CONN_02"))
    )
    (comp (ref "L4")
      (value "3.3µH")
      (footprint "eagle-import:0805")
      (libsource (lib "eagle-import") (part "INDUCTOR-0805-3.3UH"))
    )
    (comp (ref "R19")
      (value "33R")
      (footprint "eagle-import:R0402_B")
      (libsource (lib "eagle-import") (part "R-US_"))
    )
    (comp (ref "R23")
      (value "12.4k")
      (footprint "eagle-import:R0402_B")
      (libsource (lib "eagle-import") (part "R-US_"))
    )
    (comp (ref "R24")
      (value "10k")
      (footprint "eagle-import:R0402_B")
      (libsource (lib "eagle-import") (part "R-US_"))
    )
    (comp (ref "R25")
      (value "10k")
      (footprint "eagle-import:R0402_B")
      (libsource (lib "eagle-import") (part "R-US_"))
    )
    (comp (ref "R26")
      (value "1M")
      (footprint "eagle-import:R0402_B")
      (libsource (lib "eagle-import") (part "R-US_"))
    )
    (comp (ref "R31")
      (value "49R9")
      (footprint "eagle-import:R0402_B")
      (libsource (lib "eagle-import") (part "R-US_"))
    )
    (comp (ref "R32")
      (value "10R")
      (footprint "eagle-import:R0402_B")
      (libsource (lib "eagle-import") (part "R-US_"))
    )
    (comp (ref "R39")
      (value "49R9")
      (footprint "eagle-import:R0402_B")
      (libsource (lib "eagle-import") (part "R-US_"))
    )
    (comp (ref "R40")
      (value "49R9")
      (footprint "eagle-import:R0402_B")
      (libsource (lib "eagle-import") (part "R-US_"))
    )
    (comp (ref "R41")
      (value "49R9")
      (footprint "eagle-import:R0402_B")
      (libsource (lib "eagle-import") (part "R-US_"))
    )
    (comp (ref "R42")
      (value "33R")
      (footprint "eagle-import:R0402_B")
      (libsource (lib "eagle-import") (part "R-US_"))
    )
    (comp (ref "R43")
      (value "33R")
      (footprint "eagle-import:R0402_B")
      (libsource (lib "eagle-import") (part "R-US_"))
    )
    (comp (ref "R45")
      (value "33R")
      (footprint "eagle-import:R0402_B")
      (libsource (lib "eagle-import") (part "R-US_"))
    )
    (comp (ref "R46")
      (value "33R")
      (footprint "eagle-import:R0402_B")
      (libsource (lib "eagle-import") (part "R-US_"))
    )
    (comp (ref "R47")
      (value "330R")
      (footprint "eagle-import:R0402_B")
      (libsource (lib "eagle-import") (part "R-US_"))
    )
    (comp (ref "R48")
      (value "330R")
      (footprint "eagle-import:R0402_B")
      (libsource (lib "eagle-import") (part "R-US_"))
    )
    (comp (ref "R49")
      (value "10K")
      (footprint "eagle-import:R0402_B")
      (libsource (lib "eagle-import") (part "R-US_"))
    )
    (comp (ref "R50")
      (value "0R")
      (footprint "eagle-import:R-0402S")
      (libsource (lib "eagle-import") (part "RES0402S"))
    )
    (comp (ref "R51")
      (value "33R")
      (footprint "eagle-import:R0402_B")
      (libsource (lib "eagle-import") (part "R-US_"))
    )
    (comp (ref "R53")
      (value "33R")
      (footprint "eagle-import:R0402_B")
      (libsource (lib "eagle-import") (part "R-US_"))
    )
    (comp (ref "R56")
      (value "33R")
      (footprint "eagle-import:R0402_B")
      (libsource (lib "eagle-import") (part "R-US_"))
    )
    (comp (ref "R57")
      (value "33R")
      (footprint "eagle-import:R0402_B")
      (libsource (lib "eagle-import") (part "R-US_"))
    )
    (comp (ref "R59")
      (value "?10k")
      (footprint "eagle-import:R0402_B")
      (libsource (lib "eagle-import") (part "R-US_"))
    )
    (comp (ref "R60")
      (value "10k")
      (footprint "eagle-import:R0402_B")
      (libsource (lib "eagle-import") (part "R-US_"))
    )
    (comp (ref "RJ45")
      (value "HY931147A")
      (footprint "eagle-import:ARDUINO-ETHERNET-SHIELD2-V2_CONNETTORI_POE-RJ45")
      (libsource (lib "eagle-import") (part "ARDUINO-ETHERNET-SHIELD2-V2_POE_RJ45"))
    )
    (comp (ref "RN1")
      (value "10k")
      (footprint "eagle-import:4X0402ARV341")
      (libsource (lib "eagle-import") (part "4R-N0402ARV341"))
    )
    (comp (ref "RN2")
      (value "10k")
      (footprint "eagle-import:4X0402ARV341")
      (libsource (lib "eagle-import") (part "4R-N0402ARV341"))
    )
    (comp (ref "U1")
      (value "W5500")
      (footprint "eagle-import:W5500")
      (libsource (lib "eagle-import") (part "W5500"))
    )
    (comp (ref "Y1")
      (value "25MHz")
      (footprint "eagle-import:CRYSTAL-SMD-3.2X2.5MM")
      (libsource (lib "eagle-import") (part "CRYSTAL-GROUNDEDSMD-3.2X2.5"))
    )
  )
  (nets
    (net (code "1") (name "+3V3") (class "Default")
      (node (ref "C13") (pin "2") (pinfunction "P$2_2") (pintype "passive"))
      (node (ref "C2") (pin "2") (pinfunction "P$2_2") (pintype "passive"))
      (node (ref "C25") (pin "1") (pinfunction "1_1") (pintype "passive"))
      (node (ref "C3") (pin "2") (pinfunction "P$2_2") (pintype "passive"))
      (node (ref "C33") (pin "2") (pinfunction "P$2_2") (pintype "passive"))
      (node (ref "C5") (pin "1") (pinfunction "1_1") (pintype "passive"))
      (node (ref "C7") (pin "2") (pinfunction "P$2_2") (pintype "passive"))
      (node (ref "D8") (pin "1") (pinfunction "P$1_1") (pintype "bidirectional"))
      (node (ref "J31") (pin "1") (pinfunction "1_1") (pintype "passive"))
      (node (ref "L2") (pin "P$2") (pinfunction "2_P$2") (pintype "passive"))
      (node (ref "L4") (pin "1") (pinfunction "1_1") (pintype "passive"))
      (node (ref "R14") (pin "1") (pinfunction "1_1") (pintype "bidirectional"))
      (node (ref "R16") (pin "2") (pinfunction "2_2") (pintype "passive"))
      (node (ref "R2") (pin "1") (pinfunction "1_1") (pintype "passive"))
      (node (ref "R24") (pin "2") (pinfunction "2_2") (pintype "passive"))
      (node (ref "R25") (pin "2") (pinfunction "2_2") (pintype "passive"))
      (node (ref "R3") (pin "1") (pinfunction "1_1") (pintype "passive"))
      (node (ref "R30") (pin "1") (pinfunction "1_1") (pintype "passive"))
      (node (ref "R36") (pin "1") (pinfunction "1_1") (pintype "passive"))
      (node (ref "R49") (pin "2") (pinfunction "2_2") (pintype "passive"))
      (node (ref "R59") (pin "2") (pinfunction "2_2") (pintype "passive"))
      (node (ref "R60") (pin "2") (pinfunction "2_2") (pintype "passive"))
      (node (ref "RJ45") (pin "11") (pinfunction "L1Y+_11") (pintype "bidirectional"))
      (node (ref "RJ45") (pin "13") (pinfunction "L3G+_13") (pintype "bidirectional"))
      (node (ref "RN2") (pin "2") (pinfunction "1_2") (pintype "passive"))
      (node (ref "RN2") (pin "3") (pinfunction "1_3") (pintype "passive"))
      (node (ref "RN2") (pin "4") (pinfunction "1_4") (pintype "passive"))
      (node (ref "U1") (pin "28") (pinfunction "VDD_28") (pintype "passive"))
      (node (ref "U3") (pin "3") (pinfunction "VOUT_3") (pintype "power_in"))
    )
    (net (code "2") (name "+3V3A") (class "Default")
      (node (ref "C18") (pin "2") (pinfunction "P$2_2") (pintype "passive"))
      (node (ref "C19") (pin "2") (pinfunction "P$2_2") (pintype "passive"))
      (node (ref "C20") (pin "2") (pinfunction "P$2_2") (pintype "passive"))
      (node (ref "C21") (pin "2") (pinfunction "P$2_2") (pintype "passive"))
      (node (ref "C22") (pin "2") (pinfunction "P$2_2") (pintype "passive"))
      (node (ref "C23") (pin "2") (pinfunction "P$2_2") (pintype "passive"))
      (node (ref "C28") (pin "1") (pinfunction "1_1") (pintype "passive"))
      (node (ref "L4") (pin "2") (pinfunction "2_2") (pintype "passive"))
      (node (ref "R31") (pin "2") (pinfunction "2_2") (pintype "passive"))
      (node (ref "R32") (pin "2") (pinfunction "2_2") (pintype "passive"))
      (node (ref "R39") (pin "2") (pinfunction "2_2") (pintype "passive"))
      (node (ref "U1") (pin "11") (pinfunction "AVDD_11") (pintype "passive"))
      (node (ref "U1") (pin "15") (pinfunction "AVDD_15") (pintype "passive"))
      (node (ref "U1") (pin "17") (pinfunction "AVDD_17") (pintype "passive"))
      (node (ref "U1") (pin "21") (pinfunction "AVDD_21") (pintype "passive"))
      (node (ref "U1") (pin "4") (pinfunction "AVDD_4") (pintype "passive"))
      (node (ref "U1") (pin "8") (pinfunction "AVDD_8") (pintype "passive"))
    )
    (net (code "3") (name "3V3") (class "Default")
      (node (ref "J1") (pin "10") (pinfunction "P$10_10") (pintype "bidirectional"))
      (node (ref "J1") (pin "12") (pinfunction "P$12_12") (pintype "bidirectional"))
      (node (ref "J10") (pin "3") (pinfunction "3_3") (pintype "bidirectional"))
      (node (ref "J11") (pin "3") (pinfunction "3_3") (pintype "bidirectional"))
      (node (ref "J3") (pin "8") (pinfunction "8_8") (pintype "passive"))
      (node (ref "J31") (pin "2") (pinfunction "2_2") (pintype "passive"))
      (node (ref "R1") (pin "2") (pinfunction "2_2") (pintype "bidirectional"))
      (node (ref "R27") (pin "1") (pinfunction "1_1") (pintype "bidirectional"))
      (node (ref "R28") (pin "1") (pinfunction "1_1") (pintype "bidirectional"))
      (node (ref "R29") (pin "1") (pinfunction "1_1") (pintype "bidirectional"))
      (node (ref "R9") (pin "2") (pinfunction "2_2") (pintype "bidirectional"))
      (node (ref "RGB") (pin "CA") (pinfunction "1_CA") (pintype "passive"))
      (node (ref "TP27") (pin "TP") (pinfunction "PP_TP") (pintype "input"))
      (node (ref "X4") (pin "4") (pinfunction "4-VDD_4") (pintype "bidirectional"))
    )
    (net (code "4") (name "ACTLED") (class "Default")
      (node (ref "R48") (pin "2") (pinfunction "2_2") (pintype "passive"))
      (node (ref "U1") (pin "27") (pinfunction "ACTLED_27") (pintype "passive"))
    )
    (net (code "5") (name "ADC0") (class "Default")
      (node (ref "J1") (pin "23") (pinfunction "P$23_23") (pintype "bidirectional"))
      (node (ref "J3") (pin "15") (pinfunction "15_15") (pintype "passive"))
      (node (ref "TP4") (pin "TP") (pinfunction "PP_TP") (pintype "input"))
    )
    (net (code "6") (name "ADC1") (class "Default")
      (node (ref "J1") (pin "33") (pinfunction "P$33_33") (pintype "bidirectional"))
      (node (ref "J11") (pin "1") (pinfunction "1_1") (pintype "bidirectional"))
      (node (ref "J3") (pin "17") (pinfunction "17_17") (pintype "passive"))
      (node (ref "TP5") (pin "TP") (pinfunction "PP_TP") (pintype "input"))
    )
    (net (code "7") (name "ADC2") (class "Default")
      (node (ref "J1") (pin "35") (pinfunction "P$35_35") (pintype "bidirectional"))
      (node (ref "J11") (pin "2") (pinfunction "2_2") (pintype "bidirectional"))
      (node (ref "J3") (pin "19") (pinfunction "19_19") (pintype "passive"))
      (node (ref "TP6") (pin "TP") (pinfunction "PP_TP") (pintype "input"))
    )
    (net (code "8") (name "ADC3") (class "Default")
      (node (ref "J1") (pin "37") (pinfunction "P$37_37") (pintype "bidirectional"))
      (node (ref "J3") (pin "21") (pinfunction "21_21") (pintype "passive"))
      (node (ref "TP7") (pin "TP") (pinfunction "PP_TP") (pintype "input"))
    )
    (net (code "9") (name "ADC4") (class "Default")
      (node (ref "J1") (pin "41") (pinfunction "P$41_41") (pintype "bidirectional"))
      (node (ref "J3") (pin "25") (pinfunction "25_25") (pintype "passive"))
      (node (ref "TP9") (pin "TP") (pinfunction "PP_TP") (pintype "input"))
    )
    (net (code "10") (name "ADC5") (class "Default")
      (node (ref "J1") (pin "43") (pinfunction "P$43_43") (pintype "bidirectional"))
      (node (ref "J3") (pin "27") (pinfunction "27_27") (pintype "passive"))
      (node (ref "TP10") (pin "TP") (pinfunction "PP_TP") (pintype "input"))
    )
    (net (code "11") (name "ADC6") (class "Default")
      (node (ref "J1") (pin "45") (pinfunction "P$45_45") (pintype "bidirectional"))
      (node (ref "J3") (pin "29") (pinfunction "29_29") (pintype "passive"))
      (node (ref "J35") (pin "18") (pinfunction "18_18") (pintype "passive"))
      (node (ref "TP11") (pin "TP") (pinfunction "PP_TP") (pintype "input"))
    )
    (net (code "12") (name "ADC7") (class "Default")
      (node (ref "J1") (pin "47") (pinfunction "P$47_47") (pintype "bidirectional"))
      (node (ref "J3") (pin "31") (pinfunction "31_31") (pintype "passive"))
      (node (ref "R56") (pin "2") (pinfunction "2_2") (pintype "passive"))
      (node (ref "TP12") (pin "TP") (pinfunction "PP_TP") (pintype "input"))
    )
    (net (code "13") (name "AGND") (class "Default")
      (node (ref "J1") (pin "39") (pinfunction "P$39_39") (pintype "bidirectional"))
      (node (ref "J1") (pin "49") (pinfunction "P$49_49") (pintype "bidirectional"))
      (node (ref "L1") (pin "2") (pinfunction "2_2") (pintype "bidirectional"))
    )
    (net (code "14") (name "BLUE") (class "Default")
      (node (ref "J1") (pin "65") (pinfunction "P$65_65") (pintype "bidirectional"))
      (node (ref "J3") (pin "49") (pinfunction "49_49") (pintype "passive"))
      (node (ref "R15") (pin "1") (pinfunction "1_1") (pintype "bidirectional"))
      (node (ref "TP21") (pin "TP") (pinfunction "PP_TP") (pintype "input"))
    )
    (net (code "15") (name "BTST") (class "Default")
      (node (ref "C17") (pin "1") (pinfunction "1_1") (pintype "passive"))
      (node (ref "U14") (pin "21") (pinfunction "BTST_21") (pintype "bidirectional"))
    )
    (net (code "16") (name "CHGND") (class "Default")
      (node (ref "C29") (pin "P$1") (pinfunction "P$1_P$1") (pintype "passive"))
      (node (ref "RJ45") (pin "CH1") (pinfunction "CH1_CH1") (pintype "bidirectional"))
      (node (ref "RJ45") (pin "CH2") (pinfunction "CH2_CH2") (pintype "bidirectional"))
    )
    (net (code "17") (name "CS") (class "Default")
      (node (ref "J1") (pin "48") (pinfunction "P$48_48") (pintype "bidirectional"))
      (node (ref "J3") (pin "34") (pinfunction "34_34") (pintype "passive"))
      (node (ref "J35") (pin "8") (pinfunction "8_8") (pintype "passive"))
      (node (ref "TP38") (pin "TP") (pinfunction "PP_TP") (pintype "input"))
    )
    (net (code "18") (name "CTS") (class "Default")
      (node (ref "J1") (pin "40") (pinfunction "P$40_40") (pintype "bidirectional"))
      (node (ref "J12") (pin "5") (pinfunction "5_5") (pintype "passive"))
      (node (ref "J3") (pin "26") (pinfunction "26_26") (pintype "passive"))
      (node (ref "TP36") (pin "TP") (pinfunction "PP_TP") (pintype "input"))
    )
    (net (code "19") (name "ETH_CS") (class "Default")
      (node (ref "J35") (pin "7") (pinfunction "7_7") (pintype "passive"))
      (node (ref "R57") (pin "2") (pinfunction "2_2") (pintype "passive"))
    )
    (net (code "20") (name "ETH_MISO") (class "Default")
      (node (ref "J35") (pin "11") (pinfunction "11_11") (pintype "passive"))
      (node (ref "R51") (pin "2") (pinfunction "2_2") (pintype "passive"))
    )
    (net (code "21") (name "ETH_MOSI") (class "Default")
      (node (ref "J35") (pin "13") (pinfunction "13_13") (pintype "passive"))
      (node (ref "R19") (pin "2") (pinfunction "2_2") (pintype "passive"))
    )
    (net (code "22") (name "ETH_SCK") (class "Default")
      (node (ref "J35") (pin "9") (pinfunction "9_9") (pintype "passive"))
      (node (ref "R53") (pin "2") (pinfunction "2_2") (pintype "passive"))
    )
    (net (code "23") (name "GND") (class "Default")
      (node (ref "BUTTON") (pin "3") (pinfunction "P$3_3") (pintype "bidirectional"))
      (node (ref "BUTTON") (pin "4") (pinfunction "P$4_4") (pintype "bidirectional"))
      (node (ref "C1") (pin "1") (pinfunction "P$1_1") (pintype "passive"))
      (node (ref "C11") (pin "1") (pinfunction "P$1_1") (pintype "passive"))
      (node (ref "C12") (pin "1") (pinfunction "P$1_1") (pintype "passive"))
      (node (ref "C13") (pin "1") (pinfunction "P$1_1") (pintype "passive"))
      (node (ref "C14") (pin "1") (pinfunction "P$1_1") (pintype "passive"))
      (node (ref "C18") (pin "1") (pinfunction "P$1_1") (pintype "passive"))
      (node (ref "C19") (pin "1") (pinfunction "P$1_1") (pintype "passive"))
      (node (ref "C2") (pin "1") (pinfunction "P$1_1") (pintype "passive"))
      (node (ref "C20") (pin "1") (pinfunction "P$1_1") (pintype "passive"))
      (node (ref "C21") (pin "1") (pinfunction "P$1_1") (pintype "passive"))
      (node (ref "C22") (pin "1") (pinfunction "P$1_1") (pintype "passive"))
      (node (ref "C23") (pin "1") (pinfunction "P$1_1") (pintype "passive"))
      (node (ref "C24") (pin "1") (pinfunction "P$1_1") (pintype "passive"))
      (node (ref "C25") (pin "2") (pinfunction "2_2") (pintype "passive"))
      (node (ref "C26") (pin "1") (pinfunction "P$1_1") (pintype "passive"))
      (node (ref "C28") (pin "2") (pinfunction "2_2") (pintype "passive"))
      (node (ref "C29") (pin "P$2") (pinfunction "P$2_P$2") (pintype "passive"))
      (node (ref "C3") (pin "1") (pinfunction "P$1_1") (pintype "passive"))
      (node (ref "C30") (pin "1") (pinfunction "P$1_1") (pintype "passive"))
      (node (ref "C31") (pin "2") (pinfunction "2_2") (pintype "passive"))
      (node (ref "C33") (pin "1") (pinfunction "P$1_1") (pintype "passive"))
      (node (ref "C4") (pin "2") (pinfunction "2_2") (pintype "passive"))
      (node (ref "C47") (pin "2") (pinfunction "2_2") (pintype "passive"))
      (node (ref "C5") (pin "2") (pinfunction "2_2") (pintype "passive"))
      (node (ref "C54") (pin "2") (pinfunction "2_2") (pintype "passive"))
      (node (ref "C55") (pin "2") (pinfunction "2_2") (pintype "passive"))
      (node (ref "C56") (pin "2") (pinfunction "2_2") (pintype "passive"))
      (node (ref "C57") (pin "2") (pinfunction "2_2") (pintype "passive"))
      (node (ref "C58") (pin "2") (pinfunction "2_2") (pintype "passive"))
      (node (ref "C59") (pin "2") (pinfunction "2_2") (pintype "passive"))
      (node (ref "C6") (pin "1") (pinfunction "P$1_1") (pintype "passive"))
      (node (ref "C60") (pin "2") (pinfunction "2_2") (pintype "passive"))
      (node (ref "C62") (pin "2") (pinfunction "2_2") (pintype "passive"))
      (node (ref "C63") (pin "2") (pinfunction "2_2") (pintype "passive"))
      (node (ref "C64") (pin "2") (pinfunction "2_2") (pintype "passive"))
      (node (ref "C65") (pin "2") (pinfunction "2_2") (pintype "passive"))
      (node (ref "C7") (pin "1") (pinfunction "P$1_1") (pintype "passive"))
      (node (ref "D1") (pin "1") (pinfunction "1_1") (pintype "bidirectional"))
      (node (ref "D6") (pin "1") (pinfunction "1_1") (pintype "bidirectional"))
      (node (ref "DEBUG") (pin "3") (pinfunction "3_3") (pintype "bidirectional"))
      (node (ref "DEBUG") (pin "5") (pinfunction "5_5") (pintype "bidirectional"))
      (node (ref "DEBUG") (pin "9") (pinfunction "9_9") (pintype "bidirectional"))
      (node (ref "J1") (pin "1") (pinfunction "P$1_1") (pintype "bidirectional"))
      (node (ref "J1") (pin "15") (pinfunction "P$15_15") (pintype "bidirectional"))
      (node (ref "J1") (pin "21") (pinfunction "P$21_21") (pintype "bidirectional"))
      (node (ref "J1") (pin "3") (pinfunction "P$3_3") (pintype "bidirectional"))
      (node (ref "J1") (pin "5") (pinfunction "P$5_5") (pintype "bidirectional"))
      (node (ref "J1") (pin "56") (pinfunction "P$56_56") (pintype "bidirectional"))
      (node (ref "J1") (pin "7") (pinfunction "P$7_7") (pintype "bidirectional"))
      (node (ref "J1") (pin "76") (pinfunction "P$76_76") (pintype "power_in"))
      (node (ref "J1") (pin "77") (pinfunction "P$77_77") (pintype "power_in"))
      (node (ref "J1") (pin "9") (pinfunction "P$9_9") (pintype "bidirectional"))
      (node (ref "J10") (pin "4") (pinfunction "4_4") (pintype "bidirectional"))
      (node (ref "J11") (pin "4") (pinfunction "4_4") (pintype "bidirectional"))
      (node (ref "J14") (pin "2") (pinfunction "2_2") (pintype "passive"))
      (node (ref "J14") (pin "3") (pinfunction "3_3") (pintype "passive"))
      (node (ref "J15") (pin "1") (pinfunction "1_1") (pintype "passive"))
      (node (ref "J15") (pin "2") (pinfunction "2_2") (pintype "passive"))
      (node (ref "J2") (pin "2") (pinfunction "2_2") (pintype "passive"))
      (node (ref "J2") (pin "3") (pinfunction "3_3") (pintype "passive"))
      (node (ref "J3") (pin "1") (pinfunction "1_1") (pintype "passive"))
      (node (ref "J3") (pin "23") (pinfunction "23_23") (pintype "passive"))
      (node (ref "J3") (pin "3") (pinfunction "3_3") (pintype "passive"))
      (node (ref "J3") (pin "33") (pinfunction "33_33") (pintype "passive"))
      (node (ref "J3") (pin "42") (pinfunction "42_42") (pintype "passive"))
      (node (ref "J3") (pin "5") (pinfunction "5_5") (pintype "passive"))
      (node (ref "J3") (pin "59") (pinfunction "59_59") (pintype "passive"))
      (node (ref "J3") (pin "7") (pinfunction "7_7") (pintype "passive"))
      (node (ref "J3") (pin "9") (pinfunction "9_9") (pintype "passive"))
      (node (ref "J35") (pin "23") (pinfunction "23_23") (pintype "passive"))
      (node (ref "J35") (pin "24") (pinfunction "24_24") (pintype "passive"))
      (node (ref "J4") (pin "1") (pinfunction "2_1") (pintype "passive"))
      (node (ref "J6") (pin "P$1") (pinfunction "GND_P$1") (pintype "bidirectional"))
      (node (ref "L1") (pin "1") (pinfunction "1_1") (pintype "bidirectional"))
      (node (ref "LED1") (pin "2") (pinfunction "K_2") (pintype "bidirectional"))
      (node (ref "LED2") (pin "2") (pinfunction "K_2") (pintype "bidirectional"))
      (node (ref "R10") (pin "1") (pinfunction "1_1") (pintype "passive"))
      (node (ref "R20") (pin "2") (pinfunction "2_2") (pintype "bidirectional"))
      (node (ref "R23") (pin "1") (pinfunction "1_1") (pintype "passive"))
      (node (ref "R33") (pin "2") (pinfunction "2_2") (pintype "passive"))
      (node (ref "R34") (pin "2") (pinfunction "2_2") (pintype "passive"))
      (node (ref "R37") (pin "2") (pinfunction "2_2") (pintype "bidirectional"))
      (node (ref "R38") (pin "1") (pinfunction "1_1") (pintype "bidirectional"))
      (node (ref "R55") (pin "2") (pinfunction "2_2") (pintype "passive"))
      (node (ref "RESET") (pin "1") (pinfunction "P$1_1") (pintype "bidirectional"))
      (node (ref "RESET") (pin "2") (pinfunction "P$2_2") (pintype "bidirectional"))
      (node (ref "RN1") (pin "1") (pinfunction "1_1") (pintype "passive"))
      (node (ref "RN1") (pin "2") (pinfunction "1_2") (pintype "passive"))
      (node (ref "RN1") (pin "3") (pinfunction "1_3") (pintype "passive"))
      (node (ref "RN1") (pin "4") (pinfunction "1_4") (pintype "passive"))
      (node (ref "RN2") (pin "1") (pinfunction "1_1") (pintype "passive"))
      (node (ref "S4") (pin "2") (pinfunction "2_2") (pintype "bidirectional"))
      (node (ref "S4") (pin "5") (pinfunction "5_5") (pintype "bidirectional"))
      (node (ref "TP13") (pin "TP") (pinfunction "PP_TP") (pintype "input"))
      (node (ref "TP26") (pin "TP") (pinfunction "PP_TP") (pintype "input"))
      (node (ref "TP42") (pin "TP") (pinfunction "PP_TP") (pintype "input"))
      (node (ref "TP8") (pin "TP") (pinfunction "PP_TP") (pintype "input"))
      (node (ref "U$2") (pin "P$1") (pinfunction "TP_P$1") (pintype "bidirectional"))
      (node (ref "U1") (pin "14") (pinfunction "AGND_14") (pintype "passive"))
      (node (ref "U1") (pin "16") (pinfunction "AGND_16") (pintype "passive"))
      (node (ref "U1") (pin "19") (pinfunction "AGND_19") (pintype "passive"))
      (node (ref "U1") (pin "23") (pinfunction "RSVD_23") (pintype "passive"))
      (node (ref "U1") (pin "29") (pinfunction "GND_29") (pintype "passive"))
      (node (ref "U1") (pin "3") (pinfunction "AGND_3") (pintype "passive"))
      (node (ref "U1") (pin "48") (pinfunction "AGND_48") (pintype "passive"))
      (node (ref "U1") (pin "9") (pinfunction "AGND_9") (pintype "passive"))
      (node (ref "U13") (pin "1") (pinfunction "CTG_1") (pintype "bidirectional"))
      (node (ref "U13") (pin "4") (pinfunction "GND_4") (pintype "bidirectional"))
      (node (ref "U13") (pin "6") (pinfunction "QST_6") (pintype "bidirectional"))
      (node (ref "U13") (pin "EP") (pinfunction "GND_EP") (pintype "bidirectional"))
      (node (ref "U14") (pin "17") (pinfunction "PGND_17") (pintype "passive"))
      (node (ref "U14") (pin "18") (pinfunction "PGND_18") (pintype "passive"))
      (node (ref "U14") (pin "PAD") (pinfunction "PAD_PAD") (pintype "power_in"))
      (node (ref "U14") (pin "PAD@1") (pinfunction "PAD_PAD@1") (pintype "power_in"))
      (node (ref "U14") (pin "PAD@2") (pinfunction "PAD_PAD@2") (pintype "power_in"))
      (node (ref "U14") (pin "PAD@3") (pinfunction "PAD_PAD@3") (pintype "power_in"))
      (node (ref "U14") (pin "PAD@4") (pinfunction "PAD_PAD@4") (pintype "power_in"))
      (node (ref "U14") (pin "PAD@5") (pinfunction "PAD_PAD@5") (pintype "power_in"))
      (node (ref "U14") (pin "PAD@6") (pinfunction "PAD_PAD@6") (pintype "power_in"))
      (node (ref "U14") (pin "PAD@7") (pinfunction "PAD_PAD@7") (pintype "power_in"))
      (node (ref "U14") (pin "PAD@8") (pinfunction "PAD_PAD@8") (pintype "power_in"))
      (node (ref "U14") (pin "PAD@9") (pinfunction "PAD_PAD@9") (pintype "power_in"))
      (node (ref "U2") (pin "2") (pinfunction "VSS_2") (pintype "power_in"))
      (node (ref "U3") (pin "2") (pinfunction "VSS_2") (pintype "power_in"))
      (node (ref "U3") (pin "5") (pinfunction "VSS_5") (pintype "power_in"))
      (node (ref "U3") (pin "P$1") (pinfunction "VSS_P$1") (pintype "power_in"))
      (node (ref "USB1") (pin "5") (pinfunction "GND3_5") (pintype "bidirectional"))
      (node (ref "USB1") (pin "6") (pinfunction "GND_6") (pintype "bidirectional"))
      (node (ref "USB1") (pin "7") (pinfunction "GND1_7") (pintype "bidirectional"))
      (node (ref "USB1") (pin "8") (pinfunction "GND4_8") (pintype "bidirectional"))
      (node (ref "USB1") (pin "9") (pinfunction "GND5_9") (pintype "bidirectional"))
      (node (ref "USB2") (pin "4") (pinfunction "ID_4") (pintype "bidirectional"))
      (node (ref "USB2") (pin "5") (pinfunction "GND3_5") (pintype "bidirectional"))
      (node (ref "USB2") (pin "6") (pinfunction "GND_6") (pintype "bidirectional"))
      (node (ref "USB2") (pin "7") (pinfunction "GND1_7") (pintype "bidirectional"))
      (node (ref "USB2") (pin "8") (pinfunction "GND4_8") (pintype "bidirectional"))
      (node (ref "USB2") (pin "9") (pinfunction "GND5_9") (pintype "bidirectional"))
      (node (ref "X1") (pin "2") (pinfunction "2_2") (pintype "passive"))
      (node (ref "X1") (pin "3") (pinfunction "2_3") (pintype "passive"))
      (node (ref "X1") (pin "4") (pinfunction "2_4") (pintype "passive"))
      (node (ref "X1") (pin "5") (pinfunction "2_5") (pintype "passive"))
      (node (ref "X3") (pin "2") (pinfunction "2_2") (pintype "passive"))
      (node (ref "X3") (pin "3") (pinfunction "2_3") (pintype "passive"))
      (node (ref "X3") (pin "4") (pinfunction "2_4") (pintype "passive"))
      (node (ref "X3") (pin "5") (pinfunction "2_5") (pintype "passive"))
      (node (ref "X4") (pin "6") (pinfunction "6-VSS_6") (pintype "bidirectional"))
      (node (ref "X4") (pin "GND1") (pinfunction "GND_GND1") (pintype "power_in"))
      (node (ref "X4") (pin "GND2") (pinfunction "GND1_GND2") (pintype "power_in"))
      (node (ref "Y1") (pin "2") (pinfunction "3_2") (pintype "passive"))
      (node (ref "Y1") (pin "4") (pinfunction "3_4") (pintype "passive"))
      (node (ref "Z1") (pin "1") (pinfunction "1_1") (pintype "passive"))
      (node (ref "Z2") (pin "1") (pinfunction "1_1") (pintype "passive"))
      (node (ref "Z3") (pin "1") (pinfunction "1_1") (pintype "passive"))
      (node (ref "Z4") (pin "1") (pinfunction "1_1") (pintype "passive"))
      (node (ref "Z5") (pin "1") (pinfunction "1_1") (pintype "passive"))
      (node (ref "Z6") (pin "1") (pinfunction "1_1") (pintype "passive"))
    )
    (net (code "24") (name "GPIO0") (class "Default")
      (node (ref "J1") (pin "62") (pinfunction "P$62_62") (pintype "bidirectional"))
      (node (ref "J3") (pin "48") (pinfunction "48_48") (pintype "passive"))
      (node (ref "J35") (pin "16") (pinfunction "16_16") (pintype "passive"))
      (node (ref "TP45") (pin "TP") (pinfunction "PP_TP") (pintype "input"))
    )
    (net (code "25") (name "GPIO1") (class "Default")
      (node (ref "J1") (pin "64") (pinfunction "P$64_64") (pintype "bidirectional"))
      (node (ref "J3") (pin "50") (pinfunction "50_50") (pintype "passive"))
      (node (ref "TP46") (pin "TP") (pinfunction "PP_TP") (pintype "input"))
    )
    (net (code "26") (name "GREEN") (class "Default")
      (node (ref "J1") (pin "63") (pinfunction "P$63_63") (pintype "bidirectional"))
      (node (ref "J3") (pin "47") (pinfunction "47_47") (pintype "passive"))
      (node (ref "R13") (pin "1") (pinfunction "1_1") (pintype "bidirectional"))
      (node (ref "TP20") (pin "TP") (pinfunction "PP_TP") (pintype "input"))
    )
    (net (code "27") (name "ILIM") (class "Default")
      (node (ref "R33") (pin "1") (pinfunction "1_1") (pintype "passive"))
      (node (ref "U14") (pin "10") (pinfunction "ILIM_10") (pintype "output"))
    )
    (net (code "28") (name "LINKLED") (class "Default")
      (node (ref "R47") (pin "2") (pinfunction "2_2") (pintype "passive"))
      (node (ref "U1") (pin "25") (pinfunction "LINKLED_25") (pintype "passive"))
    )
    (net (code "29") (name "MISO") (class "Default")
      (node (ref "J1") (pin "50") (pinfunction "P$50_50") (pintype "bidirectional"))
      (node (ref "J3") (pin "36") (pinfunction "36_36") (pintype "passive"))
      (node (ref "J35") (pin "12") (pinfunction "12_12") (pintype "passive"))
      (node (ref "TP39") (pin "TP") (pinfunction "PP_TP") (pintype "input"))
    )
    (net (code "30") (name "MODE") (class "Default")
      (node (ref "BUTTON") (pin "1") (pinfunction "P$1_1") (pintype "bidirectional"))
      (node (ref "BUTTON") (pin "2") (pinfunction "P$2_2") (pintype "bidirectional"))
      (node (ref "J1") (pin "32") (pinfunction "P$32_32") (pintype "bidirectional"))
      (node (ref "J3") (pin "18") (pinfunction "18_18") (pintype "passive"))
      (node (ref "TP32") (pin "TP") (pinfunction "PP_TP") (pintype "input"))
      (node (ref "Z3") (pin "2") (pinfunction "2_2") (pintype "passive"))
    )
    (net (code "31") (name "MOSI") (class "Default")
      (node (ref "J1") (pin "52") (pinfunction "P$52_52") (pintype "bidirectional"))
      (node (ref "J3") (pin "38") (pinfunction "38_38") (pintype "passive"))
      (node (ref "J35") (pin "14") (pinfunction "14_14") (pintype "passive"))
      (node (ref "TP40") (pin "TP") (pinfunction "PP_TP") (pintype "input"))
    )
    (net (code "32") (name "NFC1") (class "Default")
      (node (ref "J1") (pin "17") (pinfunction "P$17_17") (pintype "bidirectional"))
      (node (ref "J3") (pin "11") (pinfunction "11_11") (pintype "passive"))
      (node (ref "NFC") (pin "2@1") (pinfunction "GND_2@1") (pintype "passive"))
      (node (ref "NFC") (pin "2@2") (pinfunction "GND_2@2") (pintype "passive"))
      (node (ref "R37") (pin "1") (pinfunction "1_1") (pintype "bidirectional"))
      (node (ref "TP1") (pin "TP") (pinfunction "PP_TP") (pintype "input"))
    )
    (net (code "33") (name "NFC2") (class "Default")
      (node (ref "J1") (pin "19") (pinfunction "P$19_19") (pintype "bidirectional"))
      (node (ref "J3") (pin "13") (pinfunction "13_13") (pintype "passive"))
      (node (ref "NFC") (pin "1") (pinfunction "1_1") (pintype "passive"))
      (node (ref "R38") (pin "2") (pinfunction "2_2") (pintype "bidirectional"))
      (node (ref "TP2") (pin "TP") (pinfunction "PP_TP") (pintype "input"))
    )
    (net (code "34") (name "Net-(C1-P$2)") (class "Default")
      (node (ref "C1") (pin "2") (pinfunction "P$2_2") (pintype "passive"))
      (node (ref "R32") (pin "1") (pinfunction "1_1") (pintype "passive"))
      (node (ref "RJ45") (pin "R4") (pinfunction "TCT_R4") (pintype "bidirectional"))
    )
    (net (code "35") (name "Net-(C11-P$2)") (class "Default")
      (node (ref "C11") (pin "2") (pinfunction "P$2_2") (pintype "passive"))
      (node (ref "R26") (pin "2") (pinfunction "2_2") (pintype "passive"))
      (node (ref "U1") (pin "30") (pinfunction "XI/CLKIN_30") (pintype "passive"))
      (node (ref "Y1") (pin "3") (pinfunction "2_3") (pintype "passive"))
    )
    (net (code "36") (name "Net-(C12-P$2)") (class "Default")
      (node (ref "C12") (pin "2") (pinfunction "P$2_2") (pintype "passive"))
      (node (ref "R50") (pin "2") (pinfunction "2_2") (pintype "bidirectional"))
      (node (ref "Y1") (pin "1") (pinfunction "1_1") (pintype "passive"))
    )
    (net (code "37") (name "Net-(C14-P$2)") (class "Default")
      (node (ref "C14") (pin "2") (pinfunction "P$2_2") (pintype "passive"))
      (node (ref "R40") (pin "1") (pinfunction "1_1") (pintype "passive"))
      (node (ref "R41") (pin "1") (pinfunction "1_1") (pintype "passive"))
      (node (ref "RJ45") (pin "R3") (pinfunction "RCT_R3") (pintype "bidirectional"))
    )
    (net (code "38") (name "Net-(C15-P$2)") (class "Default")
      (node (ref "C15") (pin "2") (pinfunction "P$2_2") (pintype "passive"))
      (node (ref "RJ45") (pin "R2") (pinfunction "RD+_R2") (pintype "bidirectional"))
    )
    (net (code "39") (name "Net-(C16-P$2)") (class "Default")
      (node (ref "C16") (pin "2") (pinfunction "P$2_2") (pintype "passive"))
      (node (ref "RJ45") (pin "R1") (pinfunction "RD-_R1") (pintype "bidirectional"))
    )
    (net (code "40") (name "Net-(C26-P$2)") (class "Default")
      (node (ref "C26") (pin "2") (pinfunction "P$2_2") (pintype "passive"))
      (node (ref "U1") (pin "22") (pinfunction "1V2O_22") (pintype "passive"))
    )
    (net (code "41") (name "Net-(D5-PadA)") (class "Default")
      (node (ref "D5") (pin "A") (pinfunction "A_A") (pintype "passive"))
      (node (ref "R44") (pin "1") (pinfunction "1_1") (pintype "passive"))
    )
    (net (code "42") (name "Net-(D7-PadANODE)") (class "Default")
      (node (ref "D7") (pin "ANODE") (pinfunction "ANODE_ANODE") (pintype "bidirectional"))
      (node (ref "J2") (pin "1") (pinfunction "1_1") (pintype "passive"))
    )
    (net (code "43") (name "Net-(D8-P$2)") (class "Default")
      (node (ref "D8") (pin "2") (pinfunction "P$2_2") (pintype "bidirectional"))
      (node (ref "DEBUG") (pin "1") (pinfunction "1_1") (pintype "bidirectional"))
      (node (ref "U$1") (pin "P$1") (pinfunction "TP_P$1") (pintype "bidirectional"))
    )
    (net (code "44") (name "Net-(F1-1)") (class "Default")
      (node (ref "D6") (pin "2") (pinfunction "2_2") (pintype "bidirectional"))
      (node (ref "F1") (pin "P$1") (pinfunction "1_P$1") (pintype "bidirectional"))
      (node (ref "USB1") (pin "1") (pinfunction "VBUS_1") (pintype "bidirectional"))
    )
    (net (code "45") (name "Net-(F2-1)") (class "Default")
      (node (ref "D1") (pin "2") (pinfunction "2_2") (pintype "bidirectional"))
      (node (ref "F2") (pin "P$1") (pinfunction "1_P$1") (pintype "bidirectional"))
      (node (ref "USB2") (pin "1") (pinfunction "VBUS_1") (pintype "bidirectional"))
    )
    (net (code "46") (name "Net-(J4-1)") (class "Default")
      (node (ref "J4") (pin "2") (pinfunction "1_2") (pintype "passive"))
      (node (ref "Q2") (pin "3") (pinfunction "3_3") (pintype "bidirectional"))
    )
    (net (code "47") (name "Net-(J7-Pad1)") (class "Default")
      (node (ref "J7") (pin "1") (pinfunction "1_1") (pintype "passive"))
      (node (ref "R44") (pin "2") (pinfunction "2_2") (pintype "passive"))
    )
    (net (code "48") (name "Net-(L2-1)") (class "Default")
      (node (ref "L2") (pin "P$1") (pinfunction "1_P$1") (pintype "passive"))
      (node (ref "U3") (pin "1") (pinfunction "LX_1") (pintype "bidirectional"))
    )
    (net (code "49") (name "Net-(LED1-A)") (class "Default")
      (node (ref "LED1") (pin "1") (pinfunction "A_1") (pintype "bidirectional"))
      (node (ref "R14") (pin "2") (pinfunction "2_2") (pintype "bidirectional"))
    )
    (net (code "50") (name "Net-(LED2-A)") (class "Default")
      (node (ref "LED2") (pin "1") (pinfunction "A_1") (pintype "bidirectional"))
      (node (ref "R52") (pin "2") (pinfunction "2_2") (pintype "bidirectional"))
    )
    (net (code "51") (name "Net-(Q2-Pad1)") (class "Default")
      (node (ref "Q2") (pin "1") (pinfunction "1_1") (pintype "bidirectional"))
      (node (ref "Q3") (pin "1") (pinfunction "1_1") (pintype "bidirectional"))
      (node (ref "R7") (pin "1") (pinfunction "1_1") (pintype "bidirectional"))
      (node (ref "R8") (pin "1") (pinfunction "1_1") (pintype "bidirectional"))
    )
    (net (code "52") (name "Net-(Q2-Pad2)") (class "Default")
      (node (ref "Q2") (pin "2") (pinfunction "2_2") (pintype "bidirectional"))
      (node (ref "Q3") (pin "2") (pinfunction "2_2") (pintype "bidirectional"))
      (node (ref "R7") (pin "2") (pinfunction "2_2") (pintype "bidirectional"))
    )
    (net (code "53") (name "Net-(R8-Pad2)") (class "Default")
      (node (ref "R8") (pin "2") (pinfunction "2_2") (pintype "bidirectional"))
      (node (ref "S4") (pin "3") (pinfunction "3_3") (pintype "bidirectional"))
      (node (ref "S4") (pin "6") (pinfunction "6_6") (pintype "bidirectional"))
    )
    (net (code "54") (name "Net-(R55-Pad1)") (class "Default")
      (node (ref "R55") (pin "1") (pinfunction "1_1") (pintype "passive"))
      (node (ref "S1") (pin "3") (pinfunction "3_3") (pintype "bidirectional"))
      (node (ref "S1") (pin "6") (pinfunction "6_6") (pintype "bidirectional"))
    )
    (net (code "55") (name "Net-(RGB-2)") (class "Default")
      (node (ref "R15") (pin "2") (pinfunction "2_2") (pintype "bidirectional"))
      (node (ref "RGB") (pin "BLUE") (pinfunction "2_BLUE") (pintype "passive"))
    )
    (net (code "56") (name "Net-(RGB-3)") (class "Default")
      (node (ref "R13") (pin "2") (pinfunction "2_2") (pintype "bidirectional"))
      (node (ref "RGB") (pin "GREEN") (pinfunction "3_GREEN") (pintype "passive"))
    )
    (net (code "57") (name "Net-(RGB-4)") (class "Default")
      (node (ref "R12") (pin "2") (pinfunction "2_2") (pintype "bidirectional"))
      (node (ref "RGB") (pin "RED") (pinfunction "4_RED") (pintype "passive"))
    )
    (net (code "58") (name "Net-(RJ45-L2Y-)") (class "Default")
      (node (ref "R48") (pin "1") (pinfunction "1_1") (pintype "passive"))
      (node (ref "RJ45") (pin "12") (pinfunction "L2Y-_12") (pintype "bidirectional"))
    )
    (net (code "59") (name "Net-(RJ45-L4G-)") (class "Default")
      (node (ref "R47") (pin "1") (pinfunction "1_1") (pintype "passive"))
      (node (ref "RJ45") (pin "14") (pinfunction "L4G-_14") (pintype "bidirectional"))
    )
    (net (code "60") (name "Net-(RN1A-2)") (class "Default")
      (node (ref "RN1") (pin "8") (pinfunction "2_8") (pintype "passive"))
      (node (ref "U1") (pin "38") (pinfunction "RSVD_38") (pintype "passive"))
    )
    (net (code "61") (name "Net-(RN1B-2)") (class "Default")
      (node (ref "RN1") (pin "7") (pinfunction "2_7") (pintype "passive"))
      (node (ref "U1") (pin "39") (pinfunction "RSVD_39") (pintype "passive"))
    )
    (net (code "62") (name "Net-(RN1C-2)") (class "Default")
      (node (ref "RN1") (pin "6") (pinfunction "2_6") (pintype "passive"))
      (node (ref "U1") (pin "40") (pinfunction "RSVD_40") (pintype "passive"))
    )
    (net (code "63") (name "Net-(RN1D-2)") (class "Default")
      (node (ref "RN1") (pin "5") (pinfunction "2_5") (pintype "passive"))
      (node (ref "U1") (pin "41") (pinfunction "RSVD_41") (pintype "passive"))
    )
    (net (code "64") (name "Net-(RN2A-2)") (class "Default")
      (node (ref "RN2") (pin "8") (pinfunction "2_8") (pintype "passive"))
      (node (ref "U1") (pin "42") (pinfunction "RSVD_42") (pintype "passive"))
    )
    (net (code "65") (name "Net-(RN2B-2)") (class "Default")
      (node (ref "RN2") (pin "7") (pinfunction "2_7") (pintype "passive"))
      (node (ref "U1") (pin "43") (pinfunction "PMODE2_43") (pintype "passive"))
    )
    (net (code "66") (name "Net-(RN2C-2)") (class "Default")
      (node (ref "RN2") (pin "6") (pinfunction "2_6") (pintype "passive"))
      (node (ref "U1") (pin "44") (pinfunction "PMODE1_44") (pintype "passive"))
    )
    (net (code "67") (name "Net-(RN2D-2)") (class "Default")
      (node (ref "RN2") (pin "5") (pinfunction "2_5") (pintype "passive"))
      (node (ref "U1") (pin "45") (pinfunction "PMODE0_45") (pintype "passive"))
    )
    (net (code "68") (name "Net-(U1-EXRES1)") (class "Default")
      (node (ref "R23") (pin "2") (pinfunction "2_2") (pintype "passive"))
      (node (ref "U1") (pin "10") (pinfunction "EXRES1_10") (pintype "passive"))
    )
    (net (code "69") (name "Net-(U1-MISO)") (class "Default")
      (node (ref "R51") (pin "1") (pinfunction "1_1") (pintype "passive"))
      (node (ref "R59") (pin "1") (pinfunction "1_1") (pintype "passive"))
      (node (ref "U1") (pin "34") (pinfunction "MISO_34") (pintype "passive"))
    )
    (net (code "70") (name "Net-(U1-MOSI)") (class "Default")
      (node (ref "R19") (pin "1") (pinfunction "1_1") (pintype "passive"))
      (node (ref "R60") (pin "1") (pinfunction "1_1") (pintype "passive"))
      (node (ref "U1") (pin "35") (pinfunction "MOSI_35") (pintype "passive"))
    )
    (net (code "71") (name "Net-(U1-RXN)") (class "Default")
      (node (ref "R46") (pin "2") (pinfunction "2_2") (pintype "passive"))
      (node (ref "U1") (pin "5") (pinfunction "RXN_5") (pintype "passive"))
    )
    (net (code "72") (name "Net-(U1-RXP)") (class "Default")
      (node (ref "R45") (pin "2") (pinfunction "2_2") (pintype "passive"))
      (node (ref "U1") (pin "6") (pinfunction "RXP_6") (pintype "passive"))
    )
    (net (code "73") (name "Net-(U1-SCLK)") (class "Default")
      (node (ref "R53") (pin "1") (pinfunction "1_1") (pintype "passive"))
      (node (ref "U1") (pin "33") (pinfunction "SCLK_33") (pintype "passive"))
    )
    (net (code "74") (name "Net-(U1-SCS_N)") (class "Default")
      (node (ref "R24") (pin "1") (pinfunction "1_1") (pintype "passive"))
      (node (ref "R57") (pin "1") (pinfunction "1_1") (pintype "passive"))
      (node (ref "U1") (pin "32") (pinfunction "SCS_N_32") (pintype "passive"))
    )
    (net (code "75") (name "Net-(U1-TOCAP)") (class "Default")
      (node (ref "C31") (pin "1") (pinfunction "1_1") (pintype "passive"))
      (node (ref "U1") (pin "20") (pinfunction "TOCAP_20") (pintype "passive"))
    )
    (net (code "76") (name "Net-(U1-TXN)") (class "Default")
      (node (ref "R43") (pin "2") (pinfunction "2_2") (pintype "passive"))
      (node (ref "U1") (pin "1") (pinfunction "TXN_1") (pintype "passive"))
    )
    (net (code "77") (name "Net-(U1-TXP)") (class "Default")
      (node (ref "R42") (pin "2") (pinfunction "2_2") (pintype "passive"))
      (node (ref "U1") (pin "2") (pinfunction "TXP_2") (pintype "passive"))
    )
    (net (code "78") (name "Net-(U1-XO)") (class "Default")
      (node (ref "R26") (pin "1") (pinfunction "1_1") (pintype "passive"))
      (node (ref "R50") (pin "1") (pinfunction "1_1") (pintype "bidirectional"))
      (node (ref "U1") (pin "31") (pinfunction "XO_31") (pintype "passive"))
    )
    (net (code "79") (name "Net-(U3-CE)") (class "Default")
      (node (ref "R11") (pin "2") (pinfunction "2_2") (pintype "passive"))
      (node (ref "U3") (pin "4") (pinfunction "CE_4") (pintype "bidirectional"))
    )
    (net (code "80") (name "Net-(U13-CELL)") (class "Default")
      (node (ref "C55") (pin "1") (pinfunction "1_1") (pintype "passive"))
      (node (ref "R54") (pin "2") (pinfunction "2_2") (pintype "passive"))
      (node (ref "U13") (pin "2") (pinfunction "CELL_2") (pintype "bidirectional"))
    )
    (net (code "81") (name "Net-(U13-VDD)") (class "Default")
      (node (ref "C54") (pin "1") (pinfunction "1_1") (pintype "passive"))
      (node (ref "R16") (pin "1") (pinfunction "1_1") (pintype "passive"))
      (node (ref "U13") (pin "3") (pinfunction "VDD_3") (pintype "bidirectional"))
    )
    (net (code "82") (name "Net-(USB1-D+)") (class "Default")
      (node (ref "R5") (pin "2") (pinfunction "2_2") (pintype "bidirectional"))
      (node (ref "USB1") (pin "3") (pinfunction "D+_3") (pintype "bidirectional"))
      (node (ref "Z1") (pin "2") (pinfunction "2_2") (pintype "passive"))
    )
    (net (code "83") (name "Net-(USB1-D-)") (class "Default")
      (node (ref "R6") (pin "2") (pinfunction "2_2") (pintype "bidirectional"))
      (node (ref "USB1") (pin "2") (pinfunction "D-_2") (pintype "bidirectional"))
      (node (ref "Z2") (pin "2") (pinfunction "2_2") (pintype "passive"))
    )
    (net (code "84") (name "Net-(USB1-ID)") (class "Default")
      (node (ref "R20") (pin "1") (pinfunction "1_1") (pintype "bidirectional"))
      (node (ref "R21") (pin "1") (pinfunction "1_1") (pintype "bidirectional"))
      (node (ref "R22") (pin "1") (pinfunction "1_1") (pintype "bidirectional"))
      (node (ref "USB1") (pin "4") (pinfunction "ID_4") (pintype "bidirectional"))
    )
    (net (code "85") (name "OTG") (class "Default")
      (node (ref "R3") (pin "2") (pinfunction "2_2") (pintype "passive"))
      (node (ref "U14") (pin "8") (pinfunction "OTG_8") (pintype "bidirectional"))
    )
    (net (code "86") (name "PMIC_SYS") (class "Default")
      (node (ref "C47") (pin "1") (pinfunction "1_1") (pintype "passive"))
      (node (ref "C58") (pin "1") (pinfunction "1_1") (pintype "passive"))
      (node (ref "C59") (pin "1") (pinfunction "1_1") (pintype "passive"))
      (node (ref "J7") (pin "2") (pinfunction "2_2") (pintype "passive"))
      (node (ref "L7") (pin "P$2") (pinfunction "2_P$2") (pintype "passive"))
      (node (ref "R4") (pin "2") (pinfunction "2_2") (pintype "bidirectional"))
      (node (ref "U14") (pin "15") (pinfunction "SYS_15") (pintype "power_in"))
      (node (ref "U14") (pin "16") (pinfunction "SYS_16") (pintype "power_in"))
      (node (ref "U2") (pin "5") (pinfunction "VIN_5") (pintype "power_in"))
    )
    (net (code "87") (name "PMID") (class "Default")
      (node (ref "C56") (pin "1") (pinfunction "1_1") (pintype "passive"))
      (node (ref "C62") (pin "1") (pinfunction "1_1") (pintype "passive"))
      (node (ref "U14") (pin "23") (pinfunction "PMID_23") (pintype "passive"))
    )
    (net (code "88") (name "PWM0") (class "Default")
      (node (ref "J1") (pin "66") (pinfunction "P$66_66") (pintype "bidirectional"))
      (node (ref "J12") (pin "1") (pinfunction "1_1") (pintype "passive"))
      (node (ref "J3") (pin "52") (pinfunction "52_52") (pintype "passive"))
      (node (ref "TP47") (pin "TP") (pinfunction "PP_TP") (pintype "input"))
    )
    (net (code "89") (name "PWM1") (class "Default")
      (node (ref "J1") (pin "68") (pinfunction "P$68_68") (pintype "bidirectional"))
      (node (ref "J12") (pin "7") (pinfunction "7_7") (pintype "passive"))
      (node (ref "J3") (pin "54") (pinfunction "54_54") (pintype "passive"))
      (node (ref "TP48") (pin "TP") (pinfunction "PP_TP") (pintype "input"))
    )
    (net (code "90") (name "PWM2") (class "Default")
      (node (ref "J1") (pin "70") (pinfunction "P$70_70") (pintype "bidirectional"))
      (node (ref "J12") (pin "9") (pinfunction "9_9") (pintype "passive"))
      (node (ref "J3") (pin "56") (pinfunction "56_56") (pintype "passive"))
      (node (ref "TP49") (pin "TP") (pinfunction "PP_TP") (pintype "input"))
    )
    (net (code "91") (name "PWM3") (class "Default")
      (node (ref "J1") (pin "72") (pinfunction "P$72_72") (pintype "bidirectional"))
      (node (ref "J12") (pin "11") (pinfunction "11_11") (pintype "passive"))
      (node (ref "J3") (pin "58") (pinfunction "58_58") (pintype "passive"))
      (node (ref "TP50") (pin "TP") (pinfunction "PP_TP") (pintype "input"))
    )
    (net (code "92") (name "RED") (class "Default")
      (node (ref "J1") (pin "61") (pinfunction "P$61_61") (pintype "bidirectional"))
      (node (ref "J3") (pin "45") (pinfunction "45_45") (pintype "passive"))
      (node (ref "R12") (pin "1") (pinfunction "1_1") (pintype "bidirectional"))
      (node (ref "TP19") (pin "TP") (pinfunction "PP_TP") (pintype "input"))
    )
    (net (code "93") (name "REGN") (class "Default")
      (node (ref "C65") (pin "1") (pinfunction "1_1") (pintype "passive"))
      (node (ref "R35") (pin "1") (pinfunction "1_1") (pintype "passive"))
      (node (ref "U14") (pin "22") (pinfunction "REGN_22") (pintype "bidirectional"))
    )
    (net (code "94") (name "RTS") (class "Default")
      (node (ref "J1") (pin "42") (pinfunction "P$42_42") (pintype "bidirectional"))
      (node (ref "J12") (pin "3") (pinfunction "3_3") (pintype "passive"))
      (node (ref "J3") (pin "28") (pinfunction "28_28") (pintype "passive"))
      (node (ref "TP37") (pin "TP") (pinfunction "PP_TP") (pintype "input"))
    )
    (net (code "95") (name "RX") (class "Default")
      (node (ref "J1") (pin "38") (pinfunction "P$38_38") (pintype "bidirectional"))
      (node (ref "J3") (pin "24") (pinfunction "24_24") (pintype "passive"))
      (node (ref "TP35") (pin "TP") (pinfunction "PP_TP") (pintype "input"))
    )
    (net (code "96") (name "RX_N") (class "Default")
      (node (ref "C16") (pin "1") (pinfunction "P$1_1") (pintype "passive"))
      (node (ref "R41") (pin "2") (pinfunction "2_2") (pintype "passive"))
      (node (ref "R46") (pin "1") (pinfunction "1_1") (pintype "passive"))
    )
    (net (code "97") (name "RX_P") (class "Default")
      (node (ref "C15") (pin "1") (pinfunction "P$1_1") (pintype "passive"))
      (node (ref "R40") (pin "2") (pinfunction "2_2") (pintype "passive"))
      (node (ref "R45") (pin "1") (pinfunction "1_1") (pintype "passive"))
    )
    (net (code "98") (name "SCK") (class "Default")
      (node (ref "J1") (pin "54") (pinfunction "P$54_54") (pintype "bidirectional"))
      (node (ref "J3") (pin "40") (pinfunction "40_40") (pintype "passive"))
      (node (ref "J35") (pin "10") (pinfunction "10_10") (pintype "passive"))
      (node (ref "TP41") (pin "TP") (pinfunction "PP_TP") (pintype "input"))
    )
    (net (code "99") (name "SCL") (class "Default")
      (node (ref "J1") (pin "20") (pinfunction "P$20_20") (pintype "bidirectional"))
      (node (ref "J10") (pin "1") (pinfunction "1_1") (pintype "bidirectional"))
      (node (ref "J3") (pin "14") (pinfunction "14_14") (pintype "passive"))
      (node (ref "J35") (pin "22") (pinfunction "22_22") (pintype "passive"))
      (node (ref "TP30") (pin "TP") (pinfunction "PP_TP") (pintype "input"))
    )
    (net (code "100") (name "SCL-P") (class "Default")
      (node (ref "J35") (pin "21") (pinfunction "21_21") (pintype "passive"))
      (node (ref "R30") (pin "2") (pinfunction "2_2") (pintype "passive"))
      (node (ref "U13") (pin "7") (pinfunction "SCL_7") (pintype "bidirectional"))
      (node (ref "U14") (pin "5") (pinfunction "SCL_5") (pintype "output"))
    )
    (net (code "101") (name "SDA") (class "Default")
      (node (ref "J1") (pin "22") (pinfunction "P$22_22") (pintype "bidirectional"))
      (node (ref "J10") (pin "2") (pinfunction "2_2") (pintype "bidirectional"))
      (node (ref "J3") (pin "16") (pinfunction "16_16") (pintype "passive"))
      (node (ref "J35") (pin "20") (pinfunction "20_20") (pintype "passive"))
      (node (ref "TP31") (pin "TP") (pinfunction "PP_TP") (pintype "input"))
    )
    (net (code "102") (name "SDA-P") (class "Default")
      (node (ref "J35") (pin "19") (pinfunction "19_19") (pintype "passive"))
      (node (ref "R36") (pin "2") (pinfunction "2_2") (pintype "passive"))
      (node (ref "U13") (pin "8") (pinfunction "SDA_8") (pintype "bidirectional"))
      (node (ref "U14") (pin "6") (pinfunction "SDA_6") (pintype "bidirectional"))
    )
    (net (code "103") (name "SD_CLK1") (class "Default")
      (node (ref "J12") (pin "4") (pinfunction "4_4") (pintype "passive"))
      (node (ref "R27") (pin "2") (pinfunction "2_2") (pintype "bidirectional"))
      (node (ref "X4") (pin "5") (pinfunction "5-CLK_5") (pintype "bidirectional"))
    )
    (net (code "104") (name "SD_CS1") (class "Default")
      (node (ref "J12") (pin "8") (pinfunction "8_8") (pintype "passive"))
      (node (ref "R28") (pin "2") (pinfunction "2_2") (pintype "bidirectional"))
      (node (ref "X4") (pin "2") (pinfunction "2-CD/DAT3_2") (pintype "bidirectional"))
    )
    (net (code "105") (name "SD_DECT") (class "Default")
      (node (ref "J12") (pin "10") (pinfunction "10_10") (pintype "passive"))
      (node (ref "R9") (pin "1") (pinfunction "1_1") (pintype "bidirectional"))
      (node (ref "X4") (pin "GND3") (pinfunction "GND2_GND3") (pintype "power_in"))
      (node (ref "X4") (pin "GND4") (pinfunction "GND3_GND4") (pintype "power_in"))
    )
    (net (code "106") (name "SD_MISO1") (class "Default")
      (node (ref "J12") (pin "2") (pinfunction "2_2") (pintype "passive"))
      (node (ref "X4") (pin "7") (pinfunction "7-DAT0_7") (pintype "bidirectional"))
    )
    (net (code "107") (name "SD_MOSI1") (class "Default")
      (node (ref "J12") (pin "6") (pinfunction "6_6") (pintype "passive"))
      (node (ref "R29") (pin "2") (pinfunction "2_2") (pintype "bidirectional"))
      (node (ref "X4") (pin "3") (pinfunction "3-CMO_3") (pintype "bidirectional"))
    )
    (net (code "108") (name "SOM0") (class "Default")
      (node (ref "J1") (pin "44") (pinfunction "P$44_44") (pintype "bidirectional"))
      (node (ref "J3") (pin "30") (pinfunction "30_30") (pintype "passive"))
      (node (ref "R17") (pin "2") (pinfunction "2_2") (pintype "bidirectional"))
      (node (ref "TP52") (pin "TP") (pinfunction "PP_TP") (pintype "input"))
    )
    (net (code "109") (name "SOM1") (class "Default")
      (node (ref "J1") (pin "46") (pinfunction "P$46_46") (pintype "bidirectional"))
      (node (ref "J3") (pin "32") (pinfunction "32_32") (pintype "passive"))
      (node (ref "R18") (pin "2") (pinfunction "2_2") (pintype "bidirectional"))
      (node (ref "TP53") (pin "TP") (pinfunction "PP_TP") (pintype "input"))
    )
    (net (code "110") (name "SOM5") (class "Default")
      (node (ref "J1") (pin "67") (pinfunction "P$67_67") (pintype "bidirectional"))
      (node (ref "J3") (pin "51") (pinfunction "51_51") (pintype "passive"))
      (node (ref "TP22") (pin "TP") (pinfunction "PP_TP") (pintype "input"))
    )
    (net (code "111") (name "SOM6") (class "Default")
      (node (ref "J1") (pin "69") (pinfunction "P$69_69") (pintype "bidirectional"))
      (node (ref "J3") (pin "53") (pinfunction "53_53") (pintype "passive"))
      (node (ref "TP23") (pin "TP") (pinfunction "PP_TP") (pintype "input"))
    )
    (net (code "112") (name "SOM7") (class "Default")
      (node (ref "J1") (pin "71") (pinfunction "P$71_71") (pintype "bidirectional"))
      (node (ref "J3") (pin "55") (pinfunction "55_55") (pintype "passive"))
      (node (ref "TP24") (pin "TP") (pinfunction "PP_TP") (pintype "input"))
    )
    (net (code "113") (name "SOM8") (class "Default")
      (node (ref "J1") (pin "73") (pinfunction "P$73_73") (pintype "bidirectional"))
      (node (ref "J3") (pin "57") (pinfunction "57_57") (pintype "passive"))
      (node (ref "TP25") (pin "TP") (pinfunction "PP_TP") (pintype "input"))
    )
    (net (code "114") (name "SOM9") (class "Default")
      (node (ref "J1") (pin "75") (pinfunction "P$75_75") (pintype "bidirectional"))
      (node (ref "J3") (pin "60") (pinfunction "60_60") (pintype "passive"))
      (node (ref "TP54") (pin "TP") (pinfunction "PP_TP") (pintype "input"))
    )
    (net (code "115") (name "SOM10") (class "Default")
      (node (ref "J1") (pin "14") (pinfunction "P$14_14") (pintype "bidirectional"))
      (node (ref "J3") (pin "10") (pinfunction "10_10") (pintype "passive"))
      (node (ref "TP28") (pin "TP") (pinfunction "PP_TP") (pintype "input"))
    )
    (net (code "116") (name "SOM11") (class "Default")
      (node (ref "J1") (pin "18") (pinfunction "P$18_18") (pintype "bidirectional"))
      (node (ref "J3") (pin "12") (pinfunction "12_12") (pintype "passive"))
      (node (ref "TP29") (pin "TP") (pinfunction "PP_TP") (pintype "input"))
    )
    (net (code "117") (name "SOM12") (class "Default")
      (node (ref "J1") (pin "58") (pinfunction "P$58_58") (pintype "bidirectional"))
      (node (ref "J3") (pin "44") (pinfunction "44_44") (pintype "passive"))
      (node (ref "TP43") (pin "TP") (pinfunction "PP_TP") (pintype "input"))
    )
    (net (code "118") (name "SOM13") (class "Default")
      (node (ref "J1") (pin "60") (pinfunction "P$60_60") (pintype "bidirectional"))
      (node (ref "J3") (pin "46") (pinfunction "46_46") (pintype "passive"))
      (node (ref "TP44") (pin "TP") (pinfunction "PP_TP") (pintype "input"))
    )
    (net (code "119") (name "SOM14") (class "Default")
      (node (ref "J1") (pin "51") (pinfunction "P$51_51") (pintype "bidirectional"))
      (node (ref "J3") (pin "35") (pinfunction "35_35") (pintype "passive"))
      (node (ref "TP14") (pin "TP") (pinfunction "PP_TP") (pintype "input"))
    )
    (net (code "120") (name "SOM15") (class "Default")
      (node (ref "J1") (pin "53") (pinfunction "P$53_53") (pintype "bidirectional"))
      (node (ref "J3") (pin "37") (pinfunction "37_37") (pintype "passive"))
      (node (ref "TP15") (pin "TP") (pinfunction "PP_TP") (pintype "input"))
    )
    (net (code "121") (name "SOM16") (class "Default")
      (node (ref "J1") (pin "55") (pinfunction "P$55_55") (pintype "bidirectional"))
      (node (ref "J3") (pin "39") (pinfunction "39_39") (pintype "passive"))
      (node (ref "TP16") (pin "TP") (pinfunction "PP_TP") (pintype "input"))
    )
    (net (code "122") (name "SOM17") (class "Default")
      (node (ref "J1") (pin "57") (pinfunction "P$57_57") (pintype "bidirectional"))
      (node (ref "J3") (pin "41") (pinfunction "41_41") (pintype "bidirectional"))
      (node (ref "TP17") (pin "TP") (pinfunction "PP_TP") (pintype "input"))
    )
    (net (code "123") (name "SOM18") (class "Default")
      (node (ref "J1") (pin "59") (pinfunction "P$59_59") (pintype "bidirectional"))
      (node (ref "J3") (pin "43") (pinfunction "43_43") (pintype "passive"))
      (node (ref "TP18") (pin "TP") (pinfunction "PP_TP") (pintype "input"))
    )
    (net (code "124") (name "STAT") (class "Default")
      (node (ref "D5") (pin "C") (pinfunction "C_C") (pintype "passive"))
      (node (ref "U14") (pin "4") (pinfunction "STAT_4") (pintype "bidirectional"))
    )
    (net (code "125") (name "SW1") (class "Default")
      (node (ref "C17") (pin "2") (pinfunction "2_2") (pintype "passive"))
      (node (ref "L7") (pin "P$1") (pinfunction "1_P$1") (pintype "passive"))
      (node (ref "U14") (pin "19") (pinfunction "SW_19") (pintype "power_in"))
      (node (ref "U14") (pin "20") (pinfunction "SW_20") (pintype "power_in"))
    )
    (net (code "126") (name "SWDCLK") (class "Default")
      (node (ref "DEBUG") (pin "4") (pinfunction "4_4") (pintype "bidirectional"))
      (node (ref "P2") (pin "P$2") (pinfunction "TP_P$2") (pintype "bidirectional"))
      (node (ref "U$10") (pin "P$1") (pinfunction "TP_P$1") (pintype "bidirectional"))
    )
    (net (code "127") (name "SWDIO") (class "Default")
      (node (ref "DEBUG") (pin "2") (pinfunction "2_2") (pintype "bidirectional"))
      (node (ref "P1") (pin "P$2") (pinfunction "TP_P$2") (pintype "bidirectional"))
      (node (ref "U$9") (pin "P$1") (pinfunction "TP_P$1") (pintype "bidirectional"))
    )
    (net (code "128") (name "SWO") (class "Default")
      (node (ref "DEBUG") (pin "6") (pinfunction "6_6") (pintype "bidirectional"))
      (node (ref "P3") (pin "P$2") (pinfunction "TP_P$2") (pintype "bidirectional"))
      (node (ref "U$11") (pin "P$1") (pinfunction "TP_P$1") (pintype "bidirectional"))
    )
    (net (code "129") (name "SYS_PWR_EN") (class "Default")
      (node (ref "R4") (pin "1") (pinfunction "1_1") (pintype "bidirectional"))
      (node (ref "S1") (pin "2") (pinfunction "2_2") (pintype "bidirectional"))
      (node (ref "S1") (pin "5") (pinfunction "5_5") (pintype "bidirectional"))
      (node (ref "U2") (pin "4") (pinfunction "CE_4") (pintype "bidirectional"))
    )
    (net (code "130") (name "TS") (class "Default")
      (node (ref "R34") (pin "1") (pinfunction "1_1") (pintype "passive"))
      (node (ref "R35") (pin "2") (pinfunction "2_2") (pintype "passive"))
      (node (ref "U14") (pin "11") (pinfunction "TS_11") (pintype "bidirectional"))
      (node (ref "U14") (pin "12") (pinfunction "~{QON}_12") (pintype "bidirectional"))
    )
    (net (code "131") (name "TX") (class "Default")
      (node (ref "J1") (pin "36") (pinfunction "P$36_36") (pintype "bidirectional"))
      (node (ref "J3") (pin "22") (pinfunction "22_22") (pintype "passive"))
      (node (ref "TP34") (pin "TP") (pinfunction "PP_TP") (pintype "input"))
    )
    (net (code "132") (name "TX_N") (class "Default")
      (node (ref "R31") (pin "1") (pinfunction "1_1") (pintype "passive"))
      (node (ref "R43") (pin "1") (pinfunction "1_1") (pintype "passive"))
      (node (ref "RJ45") (pin "R5") (pinfunction "TD-_R5") (pintype "bidirectional"))
    )
    (net (code "133") (name "TX_P") (class "Default")
      (node (ref "R39") (pin "1") (pinfunction "1_1") (pintype "passive"))
      (node (ref "R42") (pin "1") (pinfunction "1_1") (pintype "passive"))
      (node (ref "RJ45") (pin "R6") (pinfunction "TD+_R6") (pintype "bidirectional"))
    )
    (net (code "134") (name "U-VBUS") (class "Default")
      (node (ref "F2") (pin "P$2") (pinfunction "2_P$2") (pintype "bidirectional"))
      (node (ref "J35") (pin "5") (pinfunction "5_5") (pintype "passive"))
    )
    (net (code "135") (name "UB_USB_N") (class "Default")
      (node (ref "J35") (pin "2") (pinfunction "2_2") (pintype "passive"))
      (node (ref "R18") (pin "1") (pinfunction "1_1") (pintype "bidirectional"))
    )
    (net (code "136") (name "UB_USB_P") (class "Default")
      (node (ref "J35") (pin "4") (pinfunction "4_4") (pintype "passive"))
      (node (ref "R17") (pin "1") (pinfunction "1_1") (pintype "bidirectional"))
    )
    (net (code "137") (name "USBD_N") (class "Default")
      (node (ref "J1") (pin "13") (pinfunction "P$13_13") (pintype "bidirectional"))
      (node (ref "R6") (pin "1") (pinfunction "1_1") (pintype "bidirectional"))
      (node (ref "U14") (pin "3") (pinfunction "~{PG}_3") (pintype "output"))
    )
    (net (code "138") (name "USBD_P") (class "Default")
      (node (ref "J1") (pin "11") (pinfunction "P$11_11") (pintype "bidirectional"))
      (node (ref "R5") (pin "1") (pinfunction "1_1") (pintype "bidirectional"))
      (node (ref "U14") (pin "2") (pinfunction "PSEL_2") (pintype "output"))
    )
    (net (code "139") (name "USBID") (class "Default")
      (node (ref "R21") (pin "2") (pinfunction "2_2") (pintype "bidirectional"))
    )
    (net (code "140") (name "USB_DET") (class "Default")
      (node (ref "J1") (pin "74") (pinfunction "P$74_74") (pintype "bidirectional"))
      (node (ref "J35") (pin "6") (pinfunction "6_6") (pintype "passive"))
    )
    (net (code "141") (name "USER_D7") (class "Default")
      (node (ref "J12") (pin "12") (pinfunction "12_12") (pintype "passive"))
      (node (ref "R52") (pin "1") (pinfunction "1_1") (pintype "bidirectional"))
    )
    (net (code "142") (name "UVCC") (class "Default")
      (node (ref "J1") (pin "2") (pinfunction "P$2_2") (pintype "bidirectional"))
      (node (ref "J1") (pin "4") (pinfunction "P$4_4") (pintype "bidirectional"))
      (node (ref "J1") (pin "6") (pinfunction "P$6_6") (pintype "bidirectional"))
      (node (ref "J1") (pin "8") (pinfunction "P$8_8") (pintype "bidirectional"))
      (node (ref "J5") (pin "1") (pinfunction "1_1") (pintype "passive"))
    )
    (net (code "143") (name "U_N") (class "Default")
      (node (ref "J35") (pin "1") (pinfunction "1_1") (pintype "passive"))
      (node (ref "USB2") (pin "2") (pinfunction "D-_2") (pintype "bidirectional"))
      (node (ref "Z6") (pin "2") (pinfunction "2_2") (pintype "passive"))
    )
    (net (code "144") (name "U_P") (class "Default")
      (node (ref "J35") (pin "3") (pinfunction "3_3") (pintype "passive"))
      (node (ref "USB2") (pin "3") (pinfunction "D+_3") (pintype "bidirectional"))
      (node (ref "Z5") (pin "2") (pinfunction "2_2") (pintype "passive"))
    )
    (net (code "145") (name "V+") (class "Default")
      (node (ref "J16") (pin "2") (pinfunction "2_2") (pintype "passive"))
      (node (ref "RJ45") (pin "R9") (pinfunction "V+_R9") (pintype "bidirectional"))
    )
    (net (code "146") (name "V-") (class "Default")
      (node (ref "J16") (pin "1") (pinfunction "1_1") (pintype "passive"))
      (node (ref "RJ45") (pin "R10") (pinfunction "V-_R10") (pintype "bidirectional"))
    )
    (net (code "147") (name "VBAT") (class "Default")
      (node (ref "C63") (pin "1") (pinfunction "1_1") (pintype "passive"))
      (node (ref "Q3") (pin "3") (pinfunction "3_3") (pintype "bidirectional"))
      (node (ref "R54") (pin "1") (pinfunction "1_1") (pintype "passive"))
      (node (ref "U14") (pin "13") (pinfunction "BAT_13") (pintype "passive"))
      (node (ref "U14") (pin "14") (pinfunction "BAT_14") (pintype "power_in"))
    )
    (net (code "148") (name "VCC") (class "Default")
      (node (ref "C4") (pin "1") (pinfunction "1_1") (pintype "passive"))
      (node (ref "C6") (pin "2") (pinfunction "P$2_2") (pintype "passive"))
      (node (ref "J3") (pin "2") (pinfunction "2_2") (pintype "passive"))
      (node (ref "J3") (pin "4") (pinfunction "4_4") (pintype "passive"))
      (node (ref "J3") (pin "6") (pinfunction "6_6") (pintype "passive"))
      (node (ref "J5") (pin "2") (pinfunction "2_2") (pintype "passive"))
      (node (ref "R11") (pin "1") (pinfunction "1_1") (pintype "passive"))
      (node (ref "TP51") (pin "TP") (pinfunction "PP_TP") (pintype "input"))
      (node (ref "U2") (pin "1") (pinfunction "VOUT_1") (pintype "power_in"))
      (node (ref "U3") (pin "6") (pinfunction "VIN_6") (pintype "power_in"))
    )
    (net (code "149") (name "VIN") (class "Default")
      (node (ref "C57") (pin "1") (pinfunction "1_1") (pintype "passive"))
      (node (ref "C60") (pin "1") (pinfunction "1_1") (pintype "passive"))
      (node (ref "C64") (pin "1") (pinfunction "1_1") (pintype "passive"))
      (node (ref "D3") (pin "CATHODE") (pinfunction "CATHODE_CATHODE") (pintype "bidirectional"))
      (node (ref "D4") (pin "CATHODE") (pinfunction "CATHODE_CATHODE") (pintype "bidirectional"))
      (node (ref "D7") (pin "CATHODE") (pinfunction "CATHODE_CATHODE") (pintype "bidirectional"))
      (node (ref "U14") (pin "1") (pinfunction "VBUS_1") (pintype "power_in"))
      (node (ref "U14") (pin "24") (pinfunction "VBUS_24") (pintype "passive"))
    )
    (net (code "150") (name "VPOE") (class "Default")
      (node (ref "D3") (pin "ANODE") (pinfunction "ANODE_ANODE") (pintype "bidirectional"))
      (node (ref "J14") (pin "1") (pinfunction "1_1") (pintype "passive"))
    )
    (net (code "151") (name "VREG_1P8") (class "Default")
      (node (ref "R22") (pin "2") (pinfunction "2_2") (pintype "bidirectional"))
      (node (ref "TP3") (pin "P$1") (pinfunction "1_P$1") (pintype "bidirectional"))
    )
    (net (code "152") (name "VUSB") (class "Default")
      (node (ref "F1") (pin "P$2") (pinfunction "2_P$2") (pintype "bidirectional"))
      (node (ref "R61") (pin "1") (pinfunction "1_1") (pintype "passive"))
    )
    (net (code "153") (name "VUSB1") (class "Default")
      (node (ref "D4") (pin "ANODE") (pinfunction "ANODE_ANODE") (pintype "bidirectional"))
      (node (ref "J1") (pin "16") (pinfunction "P$16_16") (pintype "bidirectional"))
      (node (ref "R61") (pin "2") (pinfunction "2_2") (pintype "passive"))
    )
    (net (code "154") (name "unconnected-(DEBUG-Pad7)") (class "Default")
      (node (ref "DEBUG") (pin "7") (pinfunction "7_7") (pintype "bidirectional"))
    )
    (net (code "155") (name "unconnected-(DEBUG-Pad8)") (class "Default")
      (node (ref "DEBUG") (pin "8") (pinfunction "8_8") (pintype "bidirectional"))
    )
    (net (code "156") (name "unconnected-(RJ45-NC-PadR7)") (class "Default")
      (node (ref "RJ45") (pin "R7") (pinfunction "NC_R7") (pintype "bidirectional"))
    )
    (net (code "157") (name "unconnected-(RJ45-NC-PadR8)") (class "Default")
      (node (ref "RJ45") (pin "R8") (pinfunction "NC_R8") (pintype "bidirectional"))
    )
    (net (code "158") (name "unconnected-(S1-Pad1)") (class "Default")
      (node (ref "S1") (pin "1") (pinfunction "1_1") (pintype "bidirectional"))
    )
    (net (code "159") (name "unconnected-(S1-Pad4)") (class "Default")
      (node (ref "S1") (pin "4") (pinfunction "4_4") (pintype "bidirectional"))
    )
    (net (code "160") (name "unconnected-(S4-Pad1)") (class "Default")
      (node (ref "S4") (pin "1") (pinfunction "1_1") (pintype "bidirectional"))
    )
    (net (code "161") (name "unconnected-(S4-Pad4)") (class "Default")
      (node (ref "S4") (pin "4") (pinfunction "4_4") (pintype "bidirectional"))
    )
    (net (code "162") (name "unconnected-(U1-DNC-Pad7)") (class "Default")
      (node (ref "U1") (pin "7") (pinfunction "DNC_7") (pintype "passive"))
    )
    (net (code "163") (name "unconnected-(U1-DUPLED-Pad26)") (class "Default")
      (node (ref "U1") (pin "26") (pinfunction "DUPLED_26") (pintype "passive"))
    )
    (net (code "164") (name "unconnected-(U1-NC-Pad12)") (class "Default")
      (node (ref "U1") (pin "12") (pinfunction "NC_12") (pintype "passive"))
    )
    (net (code "165") (name "unconnected-(U1-NC-Pad13)") (class "Default")
      (node (ref "U1") (pin "13") (pinfunction "NC_13") (pintype "passive"))
    )
    (net (code "166") (name "unconnected-(U1-NC-Pad46)") (class "Default")
      (node (ref "U1") (pin "46") (pinfunction "NC_46") (pintype "passive"))
    )
    (net (code "167") (name "unconnected-(U1-NC-Pad47)") (class "Default")
      (node (ref "U1") (pin "47") (pinfunction "NC_47") (pintype "passive"))
    )
    (net (code "168") (name "unconnected-(U1-SPDLED-Pad24)") (class "Default")
      (node (ref "U1") (pin "24") (pinfunction "SPDLED_24") (pintype "passive"))
    )
    (net (code "169") (name "unconnected-(U1-VBG-Pad18)") (class "Default")
      (node (ref "U1") (pin "18") (pinfunction "VBG_18") (pintype "passive"))
    )
    (net (code "170") (name "unconnected-(U2-FLG-Pad3)") (class "Default")
      (node (ref "U2") (pin "3") (pinfunction "FLG_3") (pintype "bidirectional"))
    )
    (net (code "171") (name "unconnected-(X1-Pad1)") (class "Default")
      (node (ref "X1") (pin "1") (pinfunction "1_1") (pintype "passive"))
    )
    (net (code "172") (name "unconnected-(X3-Pad1)") (class "Default")
      (node (ref "X3") (pin "1") (pinfunction "1_1") (pintype "passive"))
    )
    (net (code "173") (name "unconnected-(X4-1-DAT2-Pad1)") (class "Default")
      (node (ref "X4") (pin "1") (pinfunction "1-DAT2_1") (pintype "bidirectional"))
    )
    (net (code "174") (name "unconnected-(X4-8-DAT1-Pad8)") (class "Default")
      (node (ref "X4") (pin "8") (pinfunction "8-DAT1_8") (pintype "bidirectional"))
    )
    (net (code "175") (name "{slash}RESET") (class "Default")
      (node (ref "C24") (pin "2") (pinfunction "P$2_2") (pintype "passive"))
      (node (ref "J1") (pin "34") (pinfunction "P$34_34") (pintype "bidirectional"))
      (node (ref "J3") (pin "20") (pinfunction "20_20") (pintype "passive"))
      (node (ref "R1") (pin "1") (pinfunction "1_1") (pintype "bidirectional"))
      (node (ref "RESET") (pin "3") (pinfunction "P$3_3") (pintype "bidirectional"))
      (node (ref "RESET") (pin "4") (pinfunction "P$4_4") (pintype "bidirectional"))
      (node (ref "TP33") (pin "TP") (pinfunction "PP_TP") (pintype "input"))
      (node (ref "Z4") (pin "2") (pinfunction "2_2") (pintype "passive"))
    )
    (net (code "176") (name "{slash}REST") (class "Default")
      (node (ref "DEBUG") (pin "10") (pinfunction "10_10") (pintype "bidirectional"))
      (node (ref "P4") (pin "P$2") (pinfunction "TP_P$2") (pintype "bidirectional"))
      (node (ref "U$12") (pin "P$1") (pinfunction "TP_P$1") (pintype "bidirectional"))
    )
    (net (code "177") (name "~{CE}") (class "Default")
      (node (ref "R10") (pin "2") (pinfunction "2_2") (pintype "passive"))
      (node (ref "U14") (pin "9") (pinfunction "~{CE}_9") (pintype "output"))
    )
    (net (code "178") (name "~{ETH_INT}") (class "Default")
      (node (ref "J35") (pin "15") (pinfunction "15_15") (pintype "passive"))
      (node (ref "R25") (pin "1") (pinfunction "1_1") (pintype "passive"))
      (node (ref "U1") (pin "36") (pinfunction "INT_N_36") (pintype "passive"))
    )
    (net (code "179") (name "~{FUEL-INT}") (class "Default")
      (node (ref "J35") (pin "17") (pinfunction "17_17") (pintype "passive"))
      (node (ref "R2") (pin "2") (pinfunction "2_2") (pintype "passive"))
      (node (ref "U13") (pin "5") (pinfunction "ALT_5") (pintype "bidirectional"))
      (node (ref "U14") (pin "7") (pinfunction "INT_7") (pintype "bidirectional"))
    )
    (net (code "180") (name "~{RESET}") (class "Default")
      (node (ref "C30") (pin "2") (pinfunction "P$2_2") (pintype "passive"))
      (node (ref "R49") (pin "1") (pinfunction "1_1") (pintype "passive"))
      (node (ref "R56") (pin "1") (pinfunction "1_1") (pintype "passive"))
      (node (ref "U1") (pin "37") (pinfunction "RST_N_37") (pintype "passive"))
    )
  )
)
